# HighVoltageMeasurementModule_1000V_multi.net
KiCad netlist of a schematic drawn in EAGLE
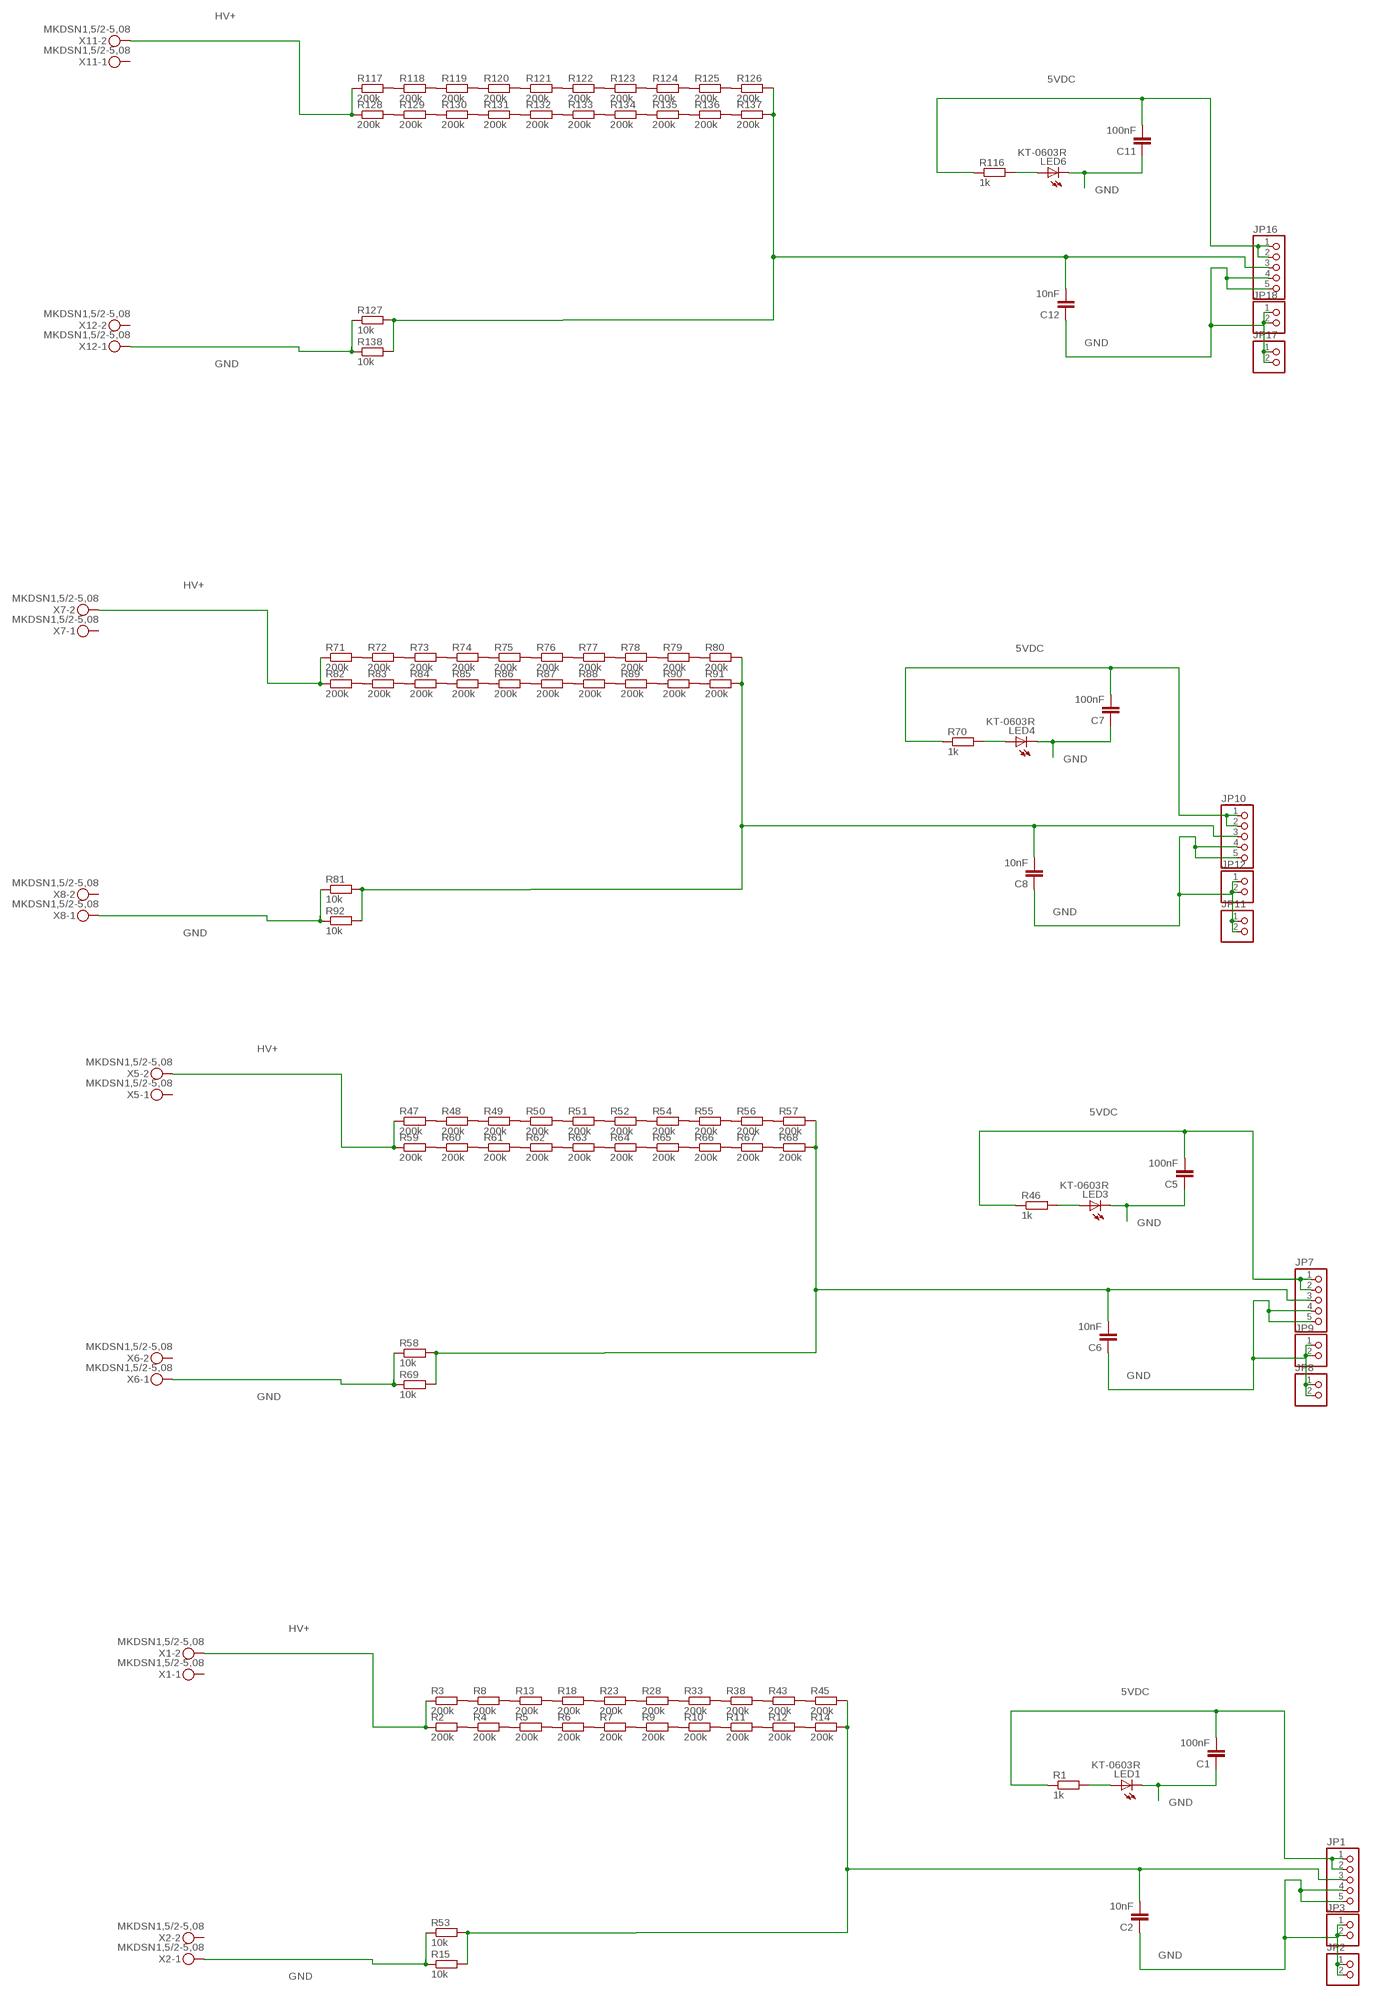
[diagram p0: schematic, sheet 1, part 1 of 3]
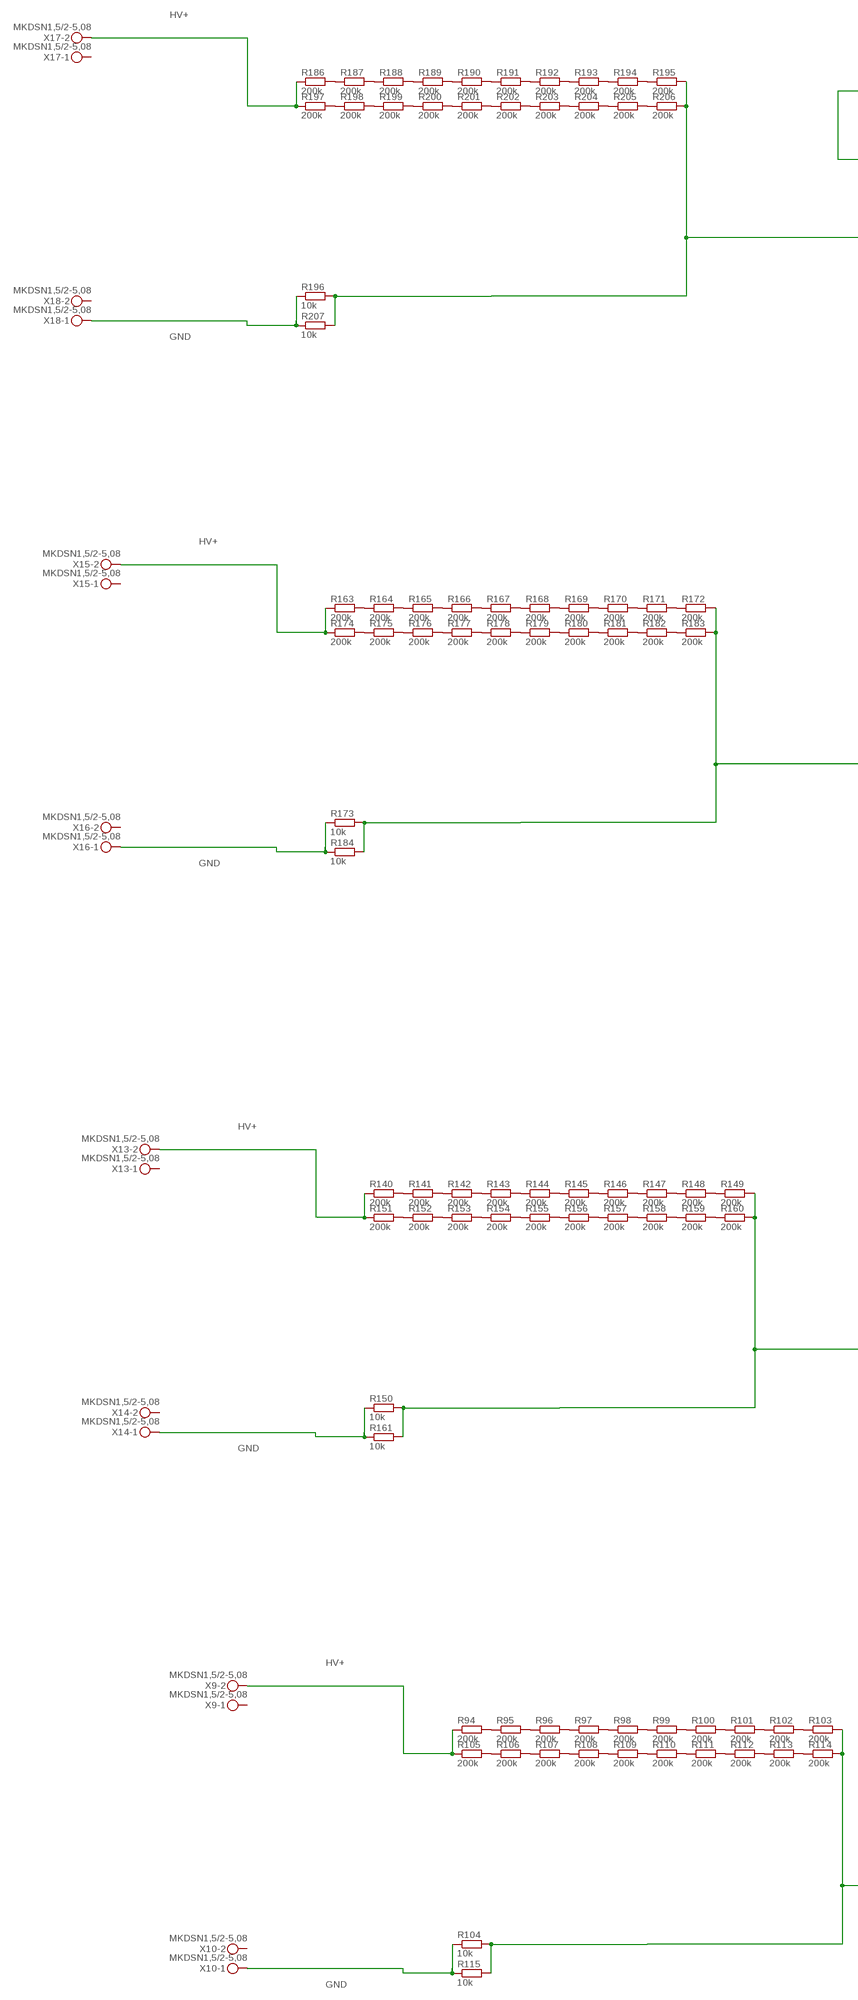
[diagram p1: schematic, sheet 1, part 2 of 3]
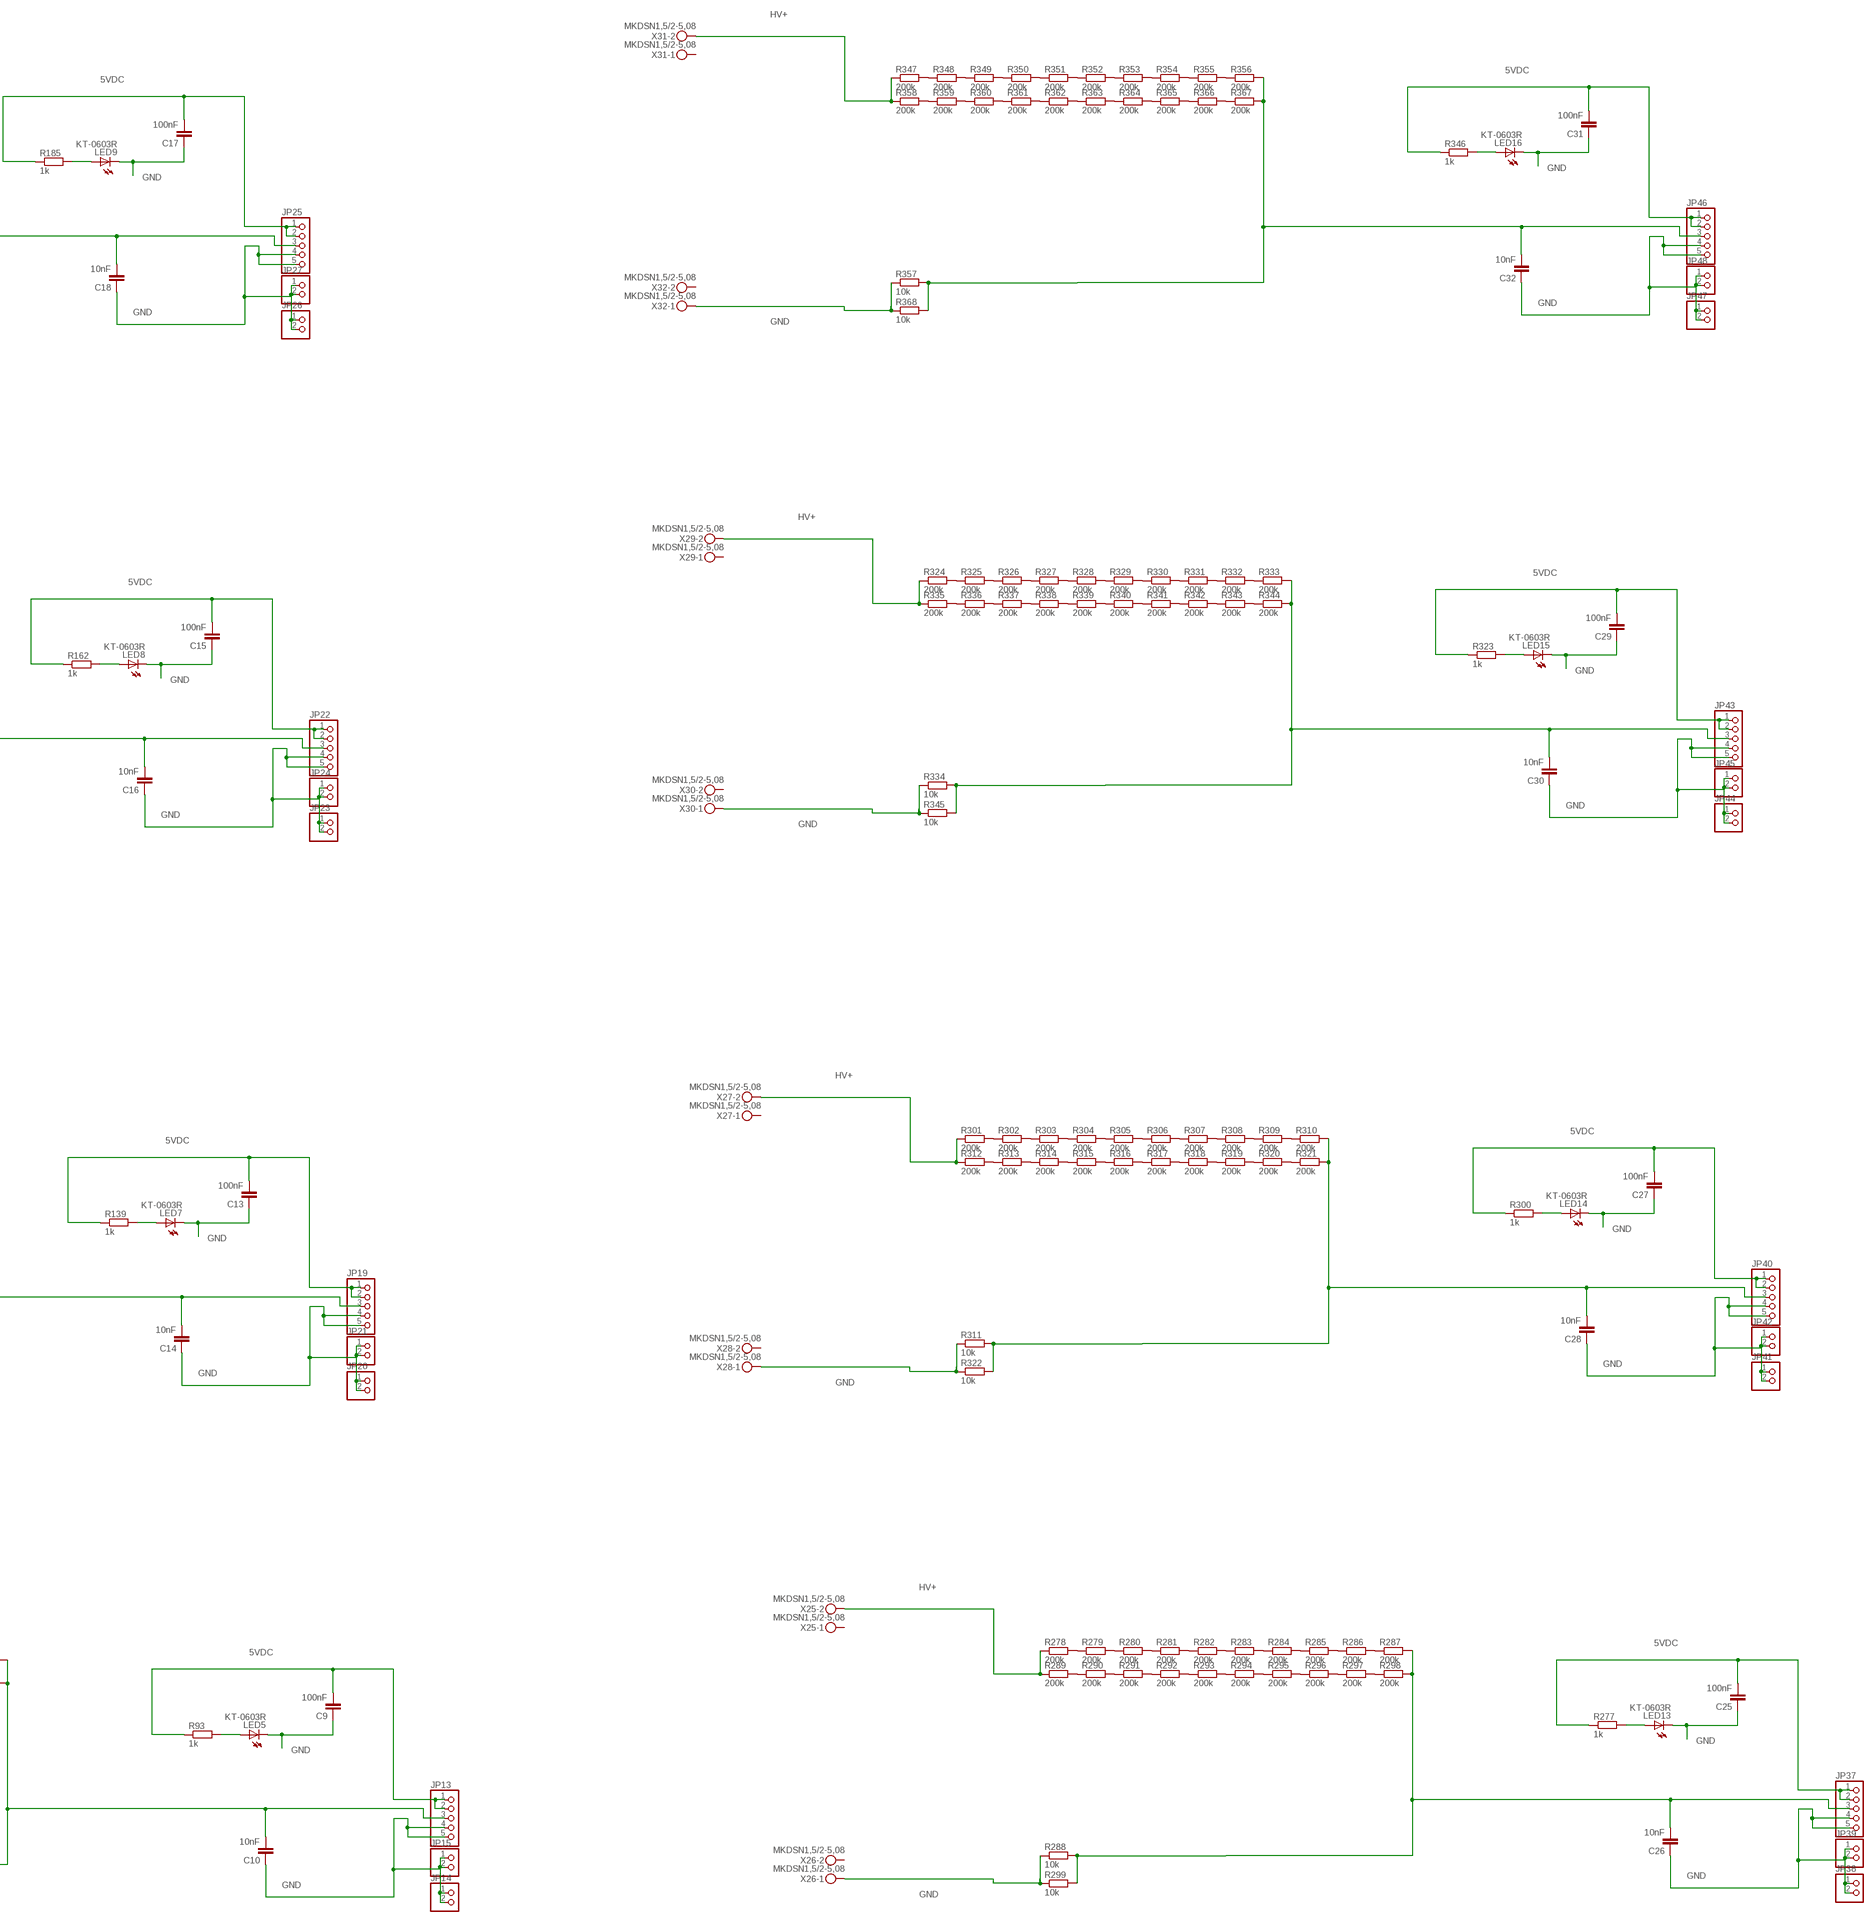
[diagram p2: schematic, sheet 1, part 3 of 3]

(export (version "E")
  (design (tool "Eeschema 10.0.6"))
  (components
    (comp (ref "C1")
      (value "100nF")
      (footprint "eagle-import:C0805")
      (libsource (lib "eagle-import") (part "C-EUC0805"))
    )
    (comp (ref "C2")
      (value "10nF")
      (footprint "eagle-import:C0805")
      (libsource (lib "eagle-import") (part "C-EUC0805"))
    )
    (comp (ref "C5")
      (value "100nF")
      (footprint "eagle-import:C0805")
      (libsource (lib "eagle-import") (part "C-EUC0805"))
    )
    (comp (ref "C6")
      (value "10nF")
      (footprint "eagle-import:C0805")
      (libsource (lib "eagle-import") (part "C-EUC0805"))
    )
    (comp (ref "C7")
      (value "100nF")
      (footprint "eagle-import:C0805")
      (libsource (lib "eagle-import") (part "C-EUC0805"))
    )
    (comp (ref "C8")
      (value "10nF")
      (footprint "eagle-import:C0805")
      (libsource (lib "eagle-import") (part "C-EUC0805"))
    )
    (comp (ref "C9")
      (value "100nF")
      (footprint "eagle-import:C0805")
      (libsource (lib "eagle-import") (part "C-EUC0805"))
    )
    (comp (ref "C10")
      (value "10nF")
      (footprint "eagle-import:C0805")
      (libsource (lib "eagle-import") (part "C-EUC0805"))
    )
    (comp (ref "C11")
      (value "100nF")
      (footprint "eagle-import:C0805")
      (libsource (lib "eagle-import") (part "C-EUC0805"))
    )
    (comp (ref "C12")
      (value "10nF")
      (footprint "eagle-import:C0805")
      (libsource (lib "eagle-import") (part "C-EUC0805"))
    )
    (comp (ref "C13")
      (value "100nF")
      (footprint "eagle-import:C0805")
      (libsource (lib "eagle-import") (part "C-EUC0805"))
    )
    (comp (ref "C14")
      (value "10nF")
      (footprint "eagle-import:C0805")
      (libsource (lib "eagle-import") (part "C-EUC0805"))
    )
    (comp (ref "C15")
      (value "100nF")
      (footprint "eagle-import:C0805")
      (libsource (lib "eagle-import") (part "C-EUC0805"))
    )
    (comp (ref "C16")
      (value "10nF")
      (footprint "eagle-import:C0805")
      (libsource (lib "eagle-import") (part "C-EUC0805"))
    )
    (comp (ref "C17")
      (value "100nF")
      (footprint "eagle-import:C0805")
      (libsource (lib "eagle-import") (part "C-EUC0805"))
    )
    (comp (ref "C18")
      (value "10nF")
      (footprint "eagle-import:C0805")
      (libsource (lib "eagle-import") (part "C-EUC0805"))
    )
    (comp (ref "C25")
      (value "100nF")
      (footprint "eagle-import:C0805")
      (libsource (lib "eagle-import") (part "C-EUC0805"))
    )
    (comp (ref "C26")
      (value "10nF")
      (footprint "eagle-import:C0805")
      (libsource (lib "eagle-import") (part "C-EUC0805"))
    )
    (comp (ref "C27")
      (value "100nF")
      (footprint "eagle-import:C0805")
      (libsource (lib "eagle-import") (part "C-EUC0805"))
    )
    (comp (ref "C28")
      (value "10nF")
      (footprint "eagle-import:C0805")
      (libsource (lib "eagle-import") (part "C-EUC0805"))
    )
    (comp (ref "C29")
      (value "100nF")
      (footprint "eagle-import:C0805")
      (libsource (lib "eagle-import") (part "C-EUC0805"))
    )
    (comp (ref "C30")
      (value "10nF")
      (footprint "eagle-import:C0805")
      (libsource (lib "eagle-import") (part "C-EUC0805"))
    )
    (comp (ref "C31")
      (value "100nF")
      (footprint "eagle-import:C0805")
      (libsource (lib "eagle-import") (part "C-EUC0805"))
    )
    (comp (ref "C32")
      (value "10nF")
      (footprint "eagle-import:C0805")
      (libsource (lib "eagle-import") (part "C-EUC0805"))
    )
    (comp (ref "JP1")
      (value "PINHD-1X5")
      (footprint "eagle-import:1X05")
      (libsource (lib "eagle-import") (part "PINHD-1X5"))
    )
    (comp (ref "JP2")
      (value "PINHD-1X2")
      (footprint "eagle-import:1X02")
      (libsource (lib "eagle-import") (part "PINHD-1X2"))
    )
    (comp (ref "JP3")
      (value "PINHD-1X2")
      (footprint "eagle-import:1X02")
      (libsource (lib "eagle-import") (part "PINHD-1X2"))
    )
    (comp (ref "JP7")
      (value "PINHD-1X5")
      (footprint "eagle-import:1X05")
      (libsource (lib "eagle-import") (part "PINHD-1X5"))
    )
    (comp (ref "JP8")
      (value "PINHD-1X2")
      (footprint "eagle-import:1X02")
      (libsource (lib "eagle-import") (part "PINHD-1X2"))
    )
    (comp (ref "JP9")
      (value "PINHD-1X2")
      (footprint "eagle-import:1X02")
      (libsource (lib "eagle-import") (part "PINHD-1X2"))
    )
    (comp (ref "JP10")
      (value "PINHD-1X5")
      (footprint "eagle-import:1X05")
      (libsource (lib "eagle-import") (part "PINHD-1X5"))
    )
    (comp (ref "JP11")
      (value "PINHD-1X2")
      (footprint "eagle-import:1X02")
      (libsource (lib "eagle-import") (part "PINHD-1X2"))
    )
    (comp (ref "JP12")
      (value "PINHD-1X2")
      (footprint "eagle-import:1X02")
      (libsource (lib "eagle-import") (part "PINHD-1X2"))
    )
    (comp (ref "JP13")
      (value "PINHD-1X5")
      (footprint "eagle-import:1X05")
      (libsource (lib "eagle-import") (part "PINHD-1X5"))
    )
    (comp (ref "JP14")
      (value "PINHD-1X2")
      (footprint "eagle-import:1X02")
      (libsource (lib "eagle-import") (part "PINHD-1X2"))
    )
    (comp (ref "JP15")
      (value "PINHD-1X2")
      (footprint "eagle-import:1X02")
      (libsource (lib "eagle-import") (part "PINHD-1X2"))
    )
    (comp (ref "JP16")
      (value "PINHD-1X5")
      (footprint "eagle-import:1X05")
      (libsource (lib "eagle-import") (part "PINHD-1X5"))
    )
    (comp (ref "JP17")
      (value "PINHD-1X2")
      (footprint "eagle-import:1X02")
      (libsource (lib "eagle-import") (part "PINHD-1X2"))
    )
    (comp (ref "JP18")
      (value "PINHD-1X2")
      (footprint "eagle-import:1X02")
      (libsource (lib "eagle-import") (part "PINHD-1X2"))
    )
    (comp (ref "JP19")
      (value "PINHD-1X5")
      (footprint "eagle-import:1X05")
      (libsource (lib "eagle-import") (part "PINHD-1X5"))
    )
    (comp (ref "JP20")
      (value "PINHD-1X2")
      (footprint "eagle-import:1X02")
      (libsource (lib "eagle-import") (part "PINHD-1X2"))
    )
    (comp (ref "JP21")
      (value "PINHD-1X2")
      (footprint "eagle-import:1X02")
      (libsource (lib "eagle-import") (part "PINHD-1X2"))
    )
    (comp (ref "JP22")
      (value "PINHD-1X5")
      (footprint "eagle-import:1X05")
      (libsource (lib "eagle-import") (part "PINHD-1X5"))
    )
    (comp (ref "JP23")
      (value "PINHD-1X2")
      (footprint "eagle-import:1X02")
      (libsource (lib "eagle-import") (part "PINHD-1X2"))
    )
    (comp (ref "JP24")
      (value "PINHD-1X2")
      (footprint "eagle-import:1X02")
      (libsource (lib "eagle-import") (part "PINHD-1X2"))
    )
    (comp (ref "JP25")
      (value "PINHD-1X5")
      (footprint "eagle-import:1X05")
      (libsource (lib "eagle-import") (part "PINHD-1X5"))
    )
    (comp (ref "JP26")
      (value "PINHD-1X2")
      (footprint "eagle-import:1X02")
      (libsource (lib "eagle-import") (part "PINHD-1X2"))
    )
    (comp (ref "JP27")
      (value "PINHD-1X2")
      (footprint "eagle-import:1X02")
      (libsource (lib "eagle-import") (part "PINHD-1X2"))
    )
    (comp (ref "JP37")
      (value "PINHD-1X5")
      (footprint "eagle-import:1X05")
      (libsource (lib "eagle-import") (part "PINHD-1X5"))
    )
    (comp (ref "JP38")
      (value "PINHD-1X2")
      (footprint "eagle-import:1X02")
      (libsource (lib "eagle-import") (part "PINHD-1X2"))
    )
    (comp (ref "JP39")
      (value "PINHD-1X2")
      (footprint "eagle-import:1X02")
      (libsource (lib "eagle-import") (part "PINHD-1X2"))
    )
    (comp (ref "JP40")
      (value "PINHD-1X5")
      (footprint "eagle-import:1X05")
      (libsource (lib "eagle-import") (part "PINHD-1X5"))
    )
    (comp (ref "JP41")
      (value "PINHD-1X2")
      (footprint "eagle-import:1X02")
      (libsource (lib "eagle-import") (part "PINHD-1X2"))
    )
    (comp (ref "JP42")
      (value "PINHD-1X2")
      (footprint "eagle-import:1X02")
      (libsource (lib "eagle-import") (part "PINHD-1X2"))
    )
    (comp (ref "JP43")
      (value "PINHD-1X5")
      (footprint "eagle-import:1X05")
      (libsource (lib "eagle-import") (part "PINHD-1X5"))
    )
    (comp (ref "JP44")
      (value "PINHD-1X2")
      (footprint "eagle-import:1X02")
      (libsource (lib "eagle-import") (part "PINHD-1X2"))
    )
    (comp (ref "JP45")
      (value "PINHD-1X2")
      (footprint "eagle-import:1X02")
      (libsource (lib "eagle-import") (part "PINHD-1X2"))
    )
    (comp (ref "JP46")
      (value "PINHD-1X5")
      (footprint "eagle-import:1X05")
      (libsource (lib "eagle-import") (part "PINHD-1X5"))
    )
    (comp (ref "JP47")
      (value "PINHD-1X2")
      (footprint "eagle-import:1X02")
      (libsource (lib "eagle-import") (part "PINHD-1X2"))
    )
    (comp (ref "JP48")
      (value "PINHD-1X2")
      (footprint "eagle-import:1X02")
      (libsource (lib "eagle-import") (part "PINHD-1X2"))
    )
    (comp (ref "LED1")
      (value "KT-0603R")
      (footprint "eagle-import:CHIPLED_0603")
      (libsource (lib "eagle-import") (part "LEDCHIPLED_0603"))
    )
    (comp (ref "LED3")
      (value "KT-0603R")
      (footprint "eagle-import:CHIPLED_0603")
      (libsource (lib "eagle-import") (part "LEDCHIPLED_0603"))
    )
    (comp (ref "LED4")
      (value "KT-0603R")
      (footprint "eagle-import:CHIPLED_0603")
      (libsource (lib "eagle-import") (part "LEDCHIPLED_0603"))
    )
    (comp (ref "LED5")
      (value "KT-0603R")
      (footprint "eagle-import:CHIPLED_0603")
      (libsource (lib "eagle-import") (part "LEDCHIPLED_0603"))
    )
    (comp (ref "LED6")
      (value "KT-0603R")
      (footprint "eagle-import:CHIPLED_0603")
      (libsource (lib "eagle-import") (part "LEDCHIPLED_0603"))
    )
    (comp (ref "LED7")
      (value "KT-0603R")
      (footprint "eagle-import:CHIPLED_0603")
      (libsource (lib "eagle-import") (part "LEDCHIPLED_0603"))
    )
    (comp (ref "LED8")
      (value "KT-0603R")
      (footprint "eagle-import:CHIPLED_0603")
      (libsource (lib "eagle-import") (part "LEDCHIPLED_0603"))
    )
    (comp (ref "LED9")
      (value "KT-0603R")
      (footprint "eagle-import:CHIPLED_0603")
      (libsource (lib "eagle-import") (part "LEDCHIPLED_0603"))
    )
    (comp (ref "LED13")
      (value "KT-0603R")
      (footprint "eagle-import:CHIPLED_0603")
      (libsource (lib "eagle-import") (part "LEDCHIPLED_0603"))
    )
    (comp (ref "LED14")
      (value "KT-0603R")
      (footprint "eagle-import:CHIPLED_0603")
      (libsource (lib "eagle-import") (part "LEDCHIPLED_0603"))
    )
    (comp (ref "LED15")
      (value "KT-0603R")
      (footprint "eagle-import:CHIPLED_0603")
      (libsource (lib "eagle-import") (part "LEDCHIPLED_0603"))
    )
    (comp (ref "LED16")
      (value "KT-0603R")
      (footprint "eagle-import:CHIPLED_0603")
      (libsource (lib "eagle-import") (part "LEDCHIPLED_0603"))
    )
    (comp (ref "R1")
      (value "1k")
      (footprint "eagle-import:R0805")
      (libsource (lib "eagle-import") (part "R-EU_R0805"))
    )
    (comp (ref "R2")
      (value "200k")
      (footprint "eagle-import:R0805")
      (libsource (lib "eagle-import") (part "R-EU_R0805"))
    )
    (comp (ref "R3")
      (value "200k")
      (footprint "eagle-import:R0805")
      (libsource (lib "eagle-import") (part "R-EU_R0805"))
    )
    (comp (ref "R4")
      (value "200k")
      (footprint "eagle-import:R0805")
      (libsource (lib "eagle-import") (part "R-EU_R0805"))
    )
    (comp (ref "R5")
      (value "200k")
      (footprint "eagle-import:R0805")
      (libsource (lib "eagle-import") (part "R-EU_R0805"))
    )
    (comp (ref "R6")
      (value "200k")
      (footprint "eagle-import:R0805")
      (libsource (lib "eagle-import") (part "R-EU_R0805"))
    )
    (comp (ref "R7")
      (value "200k")
      (footprint "eagle-import:R0805")
      (libsource (lib "eagle-import") (part "R-EU_R0805"))
    )
    (comp (ref "R8")
      (value "200k")
      (footprint "eagle-import:R0805")
      (libsource (lib "eagle-import") (part "R-EU_R0805"))
    )
    (comp (ref "R9")
      (value "200k")
      (footprint "eagle-import:R0805")
      (libsource (lib "eagle-import") (part "R-EU_R0805"))
    )
    (comp (ref "R10")
      (value "200k")
      (footprint "eagle-import:R0805")
      (libsource (lib "eagle-import") (part "R-EU_R0805"))
    )
    (comp (ref "R11")
      (value "200k")
      (footprint "eagle-import:R0805")
      (libsource (lib "eagle-import") (part "R-EU_R0805"))
    )
    (comp (ref "R12")
      (value "200k")
      (footprint "eagle-import:R0805")
      (libsource (lib "eagle-import") (part "R-EU_R0805"))
    )
    (comp (ref "R13")
      (value "200k")
      (footprint "eagle-import:R0805")
      (libsource (lib "eagle-import") (part "R-EU_R0805"))
    )
    (comp (ref "R14")
      (value "200k")
      (footprint "eagle-import:R0805")
      (libsource (lib "eagle-import") (part "R-EU_R0805"))
    )
    (comp (ref "R15")
      (value "10k")
      (footprint "eagle-import:R0805")
      (libsource (lib "eagle-import") (part "R-EU_R0805"))
    )
    (comp (ref "R18")
      (value "200k")
      (footprint "eagle-import:R0805")
      (libsource (lib "eagle-import") (part "R-EU_R0805"))
    )
    (comp (ref "R23")
      (value "200k")
      (footprint "eagle-import:R0805")
      (libsource (lib "eagle-import") (part "R-EU_R0805"))
    )
    (comp (ref "R28")
      (value "200k")
      (footprint "eagle-import:R0805")
      (libsource (lib "eagle-import") (part "R-EU_R0805"))
    )
    (comp (ref "R33")
      (value "200k")
      (footprint "eagle-import:R0805")
      (libsource (lib "eagle-import") (part "R-EU_R0805"))
    )
    (comp (ref "R38")
      (value "200k")
      (footprint "eagle-import:R0805")
      (libsource (lib "eagle-import") (part "R-EU_R0805"))
    )
    (comp (ref "R43")
      (value "200k")
      (footprint "eagle-import:R0805")
      (libsource (lib "eagle-import") (part "R-EU_R0805"))
    )
    (comp (ref "R45")
      (value "200k")
      (footprint "eagle-import:R0805")
      (libsource (lib "eagle-import") (part "R-EU_R0805"))
    )
    (comp (ref "R46")
      (value "1k")
      (footprint "eagle-import:R0805")
      (libsource (lib "eagle-import") (part "R-EU_R0805"))
    )
    (comp (ref "R47")
      (value "200k")
      (footprint "eagle-import:R0805")
      (libsource (lib "eagle-import") (part "R-EU_R0805"))
    )
    (comp (ref "R48")
      (value "200k")
      (footprint "eagle-import:R0805")
      (libsource (lib "eagle-import") (part "R-EU_R0805"))
    )
    (comp (ref "R49")
      (value "200k")
      (footprint "eagle-import:R0805")
      (libsource (lib "eagle-import") (part "R-EU_R0805"))
    )
    (comp (ref "R50")
      (value "200k")
      (footprint "eagle-import:R0805")
      (libsource (lib "eagle-import") (part "R-EU_R0805"))
    )
    (comp (ref "R51")
      (value "200k")
      (footprint "eagle-import:R0805")
      (libsource (lib "eagle-import") (part "R-EU_R0805"))
    )
    (comp (ref "R52")
      (value "200k")
      (footprint "eagle-import:R0805")
      (libsource (lib "eagle-import") (part "R-EU_R0805"))
    )
    (comp (ref "R53")
      (value "10k")
      (footprint "eagle-import:R0805")
      (libsource (lib "eagle-import") (part "R-EU_R0805"))
    )
    (comp (ref "R54")
      (value "200k")
      (footprint "eagle-import:R0805")
      (libsource (lib "eagle-import") (part "R-EU_R0805"))
    )
    (comp (ref "R55")
      (value "200k")
      (footprint "eagle-import:R0805")
      (libsource (lib "eagle-import") (part "R-EU_R0805"))
    )
    (comp (ref "R56")
      (value "200k")
      (footprint "eagle-import:R0805")
      (libsource (lib "eagle-import") (part "R-EU_R0805"))
    )
    (comp (ref "R57")
      (value "200k")
      (footprint "eagle-import:R0805")
      (libsource (lib "eagle-import") (part "R-EU_R0805"))
    )
    (comp (ref "R58")
      (value "10k")
      (footprint "eagle-import:R0805")
      (libsource (lib "eagle-import") (part "R-EU_R0805"))
    )
    (comp (ref "R59")
      (value "200k")
      (footprint "eagle-import:R0805")
      (libsource (lib "eagle-import") (part "R-EU_R0805"))
    )
    (comp (ref "R60")
      (value "200k")
      (footprint "eagle-import:R0805")
      (libsource (lib "eagle-import") (part "R-EU_R0805"))
    )
    (comp (ref "R61")
      (value "200k")
      (footprint "eagle-import:R0805")
      (libsource (lib "eagle-import") (part "R-EU_R0805"))
    )
    (comp (ref "R62")
      (value "200k")
      (footprint "eagle-import:R0805")
      (libsource (lib "eagle-import") (part "R-EU_R0805"))
    )
    (comp (ref "R63")
      (value "200k")
      (footprint "eagle-import:R0805")
      (libsource (lib "eagle-import") (part "R-EU_R0805"))
    )
    (comp (ref "R64")
      (value "200k")
      (footprint "eagle-import:R0805")
      (libsource (lib "eagle-import") (part "R-EU_R0805"))
    )
    (comp (ref "R65")
      (value "200k")
      (footprint "eagle-import:R0805")
      (libsource (lib "eagle-import") (part "R-EU_R0805"))
    )
    (comp (ref "R66")
      (value "200k")
      (footprint "eagle-import:R0805")
      (libsource (lib "eagle-import") (part "R-EU_R0805"))
    )
    (comp (ref "R67")
      (value "200k")
      (footprint "eagle-import:R0805")
      (libsource (lib "eagle-import") (part "R-EU_R0805"))
    )
    (comp (ref "R68")
      (value "200k")
      (footprint "eagle-import:R0805")
      (libsource (lib "eagle-import") (part "R-EU_R0805"))
    )
    (comp (ref "R69")
      (value "10k")
      (footprint "eagle-import:R0805")
      (libsource (lib "eagle-import") (part "R-EU_R0805"))
    )
    (comp (ref "R70")
      (value "1k")
      (footprint "eagle-import:R0805")
      (libsource (lib "eagle-import") (part "R-EU_R0805"))
    )
    (comp (ref "R71")
      (value "200k")
      (footprint "eagle-import:R0805")
      (libsource (lib "eagle-import") (part "R-EU_R0805"))
    )
    (comp (ref "R72")
      (value "200k")
      (footprint "eagle-import:R0805")
      (libsource (lib "eagle-import") (part "R-EU_R0805"))
    )
    (comp (ref "R73")
      (value "200k")
      (footprint "eagle-import:R0805")
      (libsource (lib "eagle-import") (part "R-EU_R0805"))
    )
    (comp (ref "R74")
      (value "200k")
      (footprint "eagle-import:R0805")
      (libsource (lib "eagle-import") (part "R-EU_R0805"))
    )
    (comp (ref "R75")
      (value "200k")
      (footprint "eagle-import:R0805")
      (libsource (lib "eagle-import") (part "R-EU_R0805"))
    )
    (comp (ref "R76")
      (value "200k")
      (footprint "eagle-import:R0805")
      (libsource (lib "eagle-import") (part "R-EU_R0805"))
    )
    (comp (ref "R77")
      (value "200k")
      (footprint "eagle-import:R0805")
      (libsource (lib "eagle-import") (part "R-EU_R0805"))
    )
    (comp (ref "R78")
      (value "200k")
      (footprint "eagle-import:R0805")
      (libsource (lib "eagle-import") (part "R-EU_R0805"))
    )
    (comp (ref "R79")
      (value "200k")
      (footprint "eagle-import:R0805")
      (libsource (lib "eagle-import") (part "R-EU_R0805"))
    )
    (comp (ref "R80")
      (value "200k")
      (footprint "eagle-import:R0805")
      (libsource (lib "eagle-import") (part "R-EU_R0805"))
    )
    (comp (ref "R81")
      (value "10k")
      (footprint "eagle-import:R0805")
      (libsource (lib "eagle-import") (part "R-EU_R0805"))
    )
    (comp (ref "R82")
      (value "200k")
      (footprint "eagle-import:R0805")
      (libsource (lib "eagle-import") (part "R-EU_R0805"))
    )
    (comp (ref "R83")
      (value "200k")
      (footprint "eagle-import:R0805")
      (libsource (lib "eagle-import") (part "R-EU_R0805"))
    )
    (comp (ref "R84")
      (value "200k")
      (footprint "eagle-import:R0805")
      (libsource (lib "eagle-import") (part "R-EU_R0805"))
    )
    (comp (ref "R85")
      (value "200k")
      (footprint "eagle-import:R0805")
      (libsource (lib "eagle-import") (part "R-EU_R0805"))
    )
    (comp (ref "R86")
      (value "200k")
      (footprint "eagle-import:R0805")
      (libsource (lib "eagle-import") (part "R-EU_R0805"))
    )
    (comp (ref "R87")
      (value "200k")
      (footprint "eagle-import:R0805")
      (libsource (lib "eagle-import") (part "R-EU_R0805"))
    )
    (comp (ref "R88")
      (value "200k")
      (footprint "eagle-import:R0805")
      (libsource (lib "eagle-import") (part "R-EU_R0805"))
    )
    (comp (ref "R89")
      (value "200k")
      (footprint "eagle-import:R0805")
      (libsource (lib "eagle-import") (part "R-EU_R0805"))
    )
    (comp (ref "R90")
      (value "200k")
      (footprint "eagle-import:R0805")
      (libsource (lib "eagle-import") (part "R-EU_R0805"))
    )
    (comp (ref "R91")
      (value "200k")
      (footprint "eagle-import:R0805")
      (libsource (lib "eagle-import") (part "R-EU_R0805"))
    )
    (comp (ref "R92")
      (value "10k")
      (footprint "eagle-import:R0805")
      (libsource (lib "eagle-import") (part "R-EU_R0805"))
    )
    (comp (ref "R93")
      (value "1k")
      (footprint "eagle-import:R0805")
      (libsource (lib "eagle-import") (part "R-EU_R0805"))
    )
    (comp (ref "R94")
      (value "200k")
      (footprint "eagle-import:R0805")
      (libsource (lib "eagle-import") (part "R-EU_R0805"))
    )
    (comp (ref "R95")
      (value "200k")
      (footprint "eagle-import:R0805")
      (libsource (lib "eagle-import") (part "R-EU_R0805"))
    )
    (comp (ref "R96")
      (value "200k")
      (footprint "eagle-import:R0805")
      (libsource (lib "eagle-import") (part "R-EU_R0805"))
    )
    (comp (ref "R97")
      (value "200k")
      (footprint "eagle-import:R0805")
      (libsource (lib "eagle-import") (part "R-EU_R0805"))
    )
    (comp (ref "R98")
      (value "200k")
      (footprint "eagle-import:R0805")
      (libsource (lib "eagle-import") (part "R-EU_R0805"))
    )
    (comp (ref "R99")
      (value "200k")
      (footprint "eagle-import:R0805")
      (libsource (lib "eagle-import") (part "R-EU_R0805"))
    )
    (comp (ref "R100")
      (value "200k")
      (footprint "eagle-import:R0805")
      (libsource (lib "eagle-import") (part "R-EU_R0805"))
    )
    (comp (ref "R101")
      (value "200k")
      (footprint "eagle-import:R0805")
      (libsource (lib "eagle-import") (part "R-EU_R0805"))
    )
    (comp (ref "R102")
      (value "200k")
      (footprint "eagle-import:R0805")
      (libsource (lib "eagle-import") (part "R-EU_R0805"))
    )
    (comp (ref "R103")
      (value "200k")
      (footprint "eagle-import:R0805")
      (libsource (lib "eagle-import") (part "R-EU_R0805"))
    )
    (comp (ref "R104")
      (value "10k")
      (footprint "eagle-import:R0805")
      (libsource (lib "eagle-import") (part "R-EU_R0805"))
    )
    (comp (ref "R105")
      (value "200k")
      (footprint "eagle-import:R0805")
      (libsource (lib "eagle-import") (part "R-EU_R0805"))
    )
    (comp (ref "R106")
      (value "200k")
      (footprint "eagle-import:R0805")
      (libsource (lib "eagle-import") (part "R-EU_R0805"))
    )
    (comp (ref "R107")
      (value "200k")
      (footprint "eagle-import:R0805")
      (libsource (lib "eagle-import") (part "R-EU_R0805"))
    )
    (comp (ref "R108")
      (value "200k")
      (footprint "eagle-import:R0805")
      (libsource (lib "eagle-import") (part "R-EU_R0805"))
    )
    (comp (ref "R109")
      (value "200k")
      (footprint "eagle-import:R0805")
      (libsource (lib "eagle-import") (part "R-EU_R0805"))
    )
    (comp (ref "R110")
      (value "200k")
      (footprint "eagle-import:R0805")
      (libsource (lib "eagle-import") (part "R-EU_R0805"))
    )
    (comp (ref "R111")
      (value "200k")
      (footprint "eagle-import:R0805")
      (libsource (lib "eagle-import") (part "R-EU_R0805"))
    )
    (comp (ref "R112")
      (value "200k")
      (footprint "eagle-import:R0805")
      (libsource (lib "eagle-import") (part "R-EU_R0805"))
    )
    (comp (ref "R113")
      (value "200k")
      (footprint "eagle-import:R0805")
      (libsource (lib "eagle-import") (part "R-EU_R0805"))
    )
    (comp (ref "R114")
      (value "200k")
      (footprint "eagle-import:R0805")
      (libsource (lib "eagle-import") (part "R-EU_R0805"))
    )
    (comp (ref "R115")
      (value "10k")
      (footprint "eagle-import:R0805")
      (libsource (lib "eagle-import") (part "R-EU_R0805"))
    )
    (comp (ref "R116")
      (value "1k")
      (footprint "eagle-import:R0805")
      (libsource (lib "eagle-import") (part "R-EU_R0805"))
    )
    (comp (ref "R117")
      (value "200k")
      (footprint "eagle-import:R0805")
      (libsource (lib "eagle-import") (part "R-EU_R0805"))
    )
    (comp (ref "R118")
      (value "200k")
      (footprint "eagle-import:R0805")
      (libsource (lib "eagle-import") (part "R-EU_R0805"))
    )
    (comp (ref "R119")
      (value "200k")
      (footprint "eagle-import:R0805")
      (libsource (lib "eagle-import") (part "R-EU_R0805"))
    )
    (comp (ref "R120")
      (value "200k")
      (footprint "eagle-import:R0805")
      (libsource (lib "eagle-import") (part "R-EU_R0805"))
    )
    (comp (ref "R121")
      (value "200k")
      (footprint "eagle-import:R0805")
      (libsource (lib "eagle-import") (part "R-EU_R0805"))
    )
    (comp (ref "R122")
      (value "200k")
      (footprint "eagle-import:R0805")
      (libsource (lib "eagle-import") (part "R-EU_R0805"))
    )
    (comp (ref "R123")
      (value "200k")
      (footprint "eagle-import:R0805")
      (libsource (lib "eagle-import") (part "R-EU_R0805"))
    )
    (comp (ref "R124")
      (value "200k")
      (footprint "eagle-import:R0805")
      (libsource (lib "eagle-import") (part "R-EU_R0805"))
    )
    (comp (ref "R125")
      (value "200k")
      (footprint "eagle-import:R0805")
      (libsource (lib "eagle-import") (part "R-EU_R0805"))
    )
    (comp (ref "R126")
      (value "200k")
      (footprint "eagle-import:R0805")
      (libsource (lib "eagle-import") (part "R-EU_R0805"))
    )
    (comp (ref "R127")
      (value "10k")
      (footprint "eagle-import:R0805")
      (libsource (lib "eagle-import") (part "R-EU_R0805"))
    )
    (comp (ref "R128")
      (value "200k")
      (footprint "eagle-import:R0805")
      (libsource (lib "eagle-import") (part "R-EU_R0805"))
    )
    (comp (ref "R129")
      (value "200k")
      (footprint "eagle-import:R0805")
      (libsource (lib "eagle-import") (part "R-EU_R0805"))
    )
    (comp (ref "R130")
      (value "200k")
      (footprint "eagle-import:R0805")
      (libsource (lib "eagle-import") (part "R-EU_R0805"))
    )
    (comp (ref "R131")
      (value "200k")
      (footprint "eagle-import:R0805")
      (libsource (lib "eagle-import") (part "R-EU_R0805"))
    )
    (comp (ref "R132")
      (value "200k")
      (footprint "eagle-import:R0805")
      (libsource (lib "eagle-import") (part "R-EU_R0805"))
    )
    (comp (ref "R133")
      (value "200k")
      (footprint "eagle-import:R0805")
      (libsource (lib "eagle-import") (part "R-EU_R0805"))
    )
    (comp (ref "R134")
      (value "200k")
      (footprint "eagle-import:R0805")
      (libsource (lib "eagle-import") (part "R-EU_R0805"))
    )
    (comp (ref "R135")
      (value "200k")
      (footprint "eagle-import:R0805")
      (libsource (lib "eagle-import") (part "R-EU_R0805"))
    )
    (comp (ref "R136")
      (value "200k")
      (footprint "eagle-import:R0805")
      (libsource (lib "eagle-import") (part "R-EU_R0805"))
    )
    (comp (ref "R137")
      (value "200k")
      (footprint "eagle-import:R0805")
      (libsource (lib "eagle-import") (part "R-EU_R0805"))
    )
    (comp (ref "R138")
      (value "10k")
      (footprint "eagle-import:R0805")
      (libsource (lib "eagle-import") (part "R-EU_R0805"))
    )
    (comp (ref "R139")
      (value "1k")
      (footprint "eagle-import:R0805")
      (libsource (lib "eagle-import") (part "R-EU_R0805"))
    )
    (comp (ref "R140")
      (value "200k")
      (footprint "eagle-import:R0805")
      (libsource (lib "eagle-import") (part "R-EU_R0805"))
    )
    (comp (ref "R141")
      (value "200k")
      (footprint "eagle-import:R0805")
      (libsource (lib "eagle-import") (part "R-EU_R0805"))
    )
    (comp (ref "R142")
      (value "200k")
      (footprint "eagle-import:R0805")
      (libsource (lib "eagle-import") (part "R-EU_R0805"))
    )
    (comp (ref "R143")
      (value "200k")
      (footprint "eagle-import:R0805")
      (libsource (lib "eagle-import") (part "R-EU_R0805"))
    )
    (comp (ref "R144")
      (value "200k")
      (footprint "eagle-import:R0805")
      (libsource (lib "eagle-import") (part "R-EU_R0805"))
    )
    (comp (ref "R145")
      (value "200k")
      (footprint "eagle-import:R0805")
      (libsource (lib "eagle-import") (part "R-EU_R0805"))
    )
    (comp (ref "R146")
      (value "200k")
      (footprint "eagle-import:R0805")
      (libsource (lib "eagle-import") (part "R-EU_R0805"))
    )
    (comp (ref "R147")
      (value "200k")
      (footprint "eagle-import:R0805")
      (libsource (lib "eagle-import") (part "R-EU_R0805"))
    )
    (comp (ref "R148")
      (value "200k")
      (footprint "eagle-import:R0805")
      (libsource (lib "eagle-import") (part "R-EU_R0805"))
    )
    (comp (ref "R149")
      (value "200k")
      (footprint "eagle-import:R0805")
      (libsource (lib "eagle-import") (part "R-EU_R0805"))
    )
    (comp (ref "R150")
      (value "10k")
      (footprint "eagle-import:R0805")
      (libsource (lib "eagle-import") (part "R-EU_R0805"))
    )
    (comp (ref "R151")
      (value "200k")
      (footprint "eagle-import:R0805")
      (libsource (lib "eagle-import") (part "R-EU_R0805"))
    )
    (comp (ref "R152")
      (value "200k")
      (footprint "eagle-import:R0805")
      (libsource (lib "eagle-import") (part "R-EU_R0805"))
    )
    (comp (ref "R153")
      (value "200k")
      (footprint "eagle-import:R0805")
      (libsource (lib "eagle-import") (part "R-EU_R0805"))
    )
    (comp (ref "R154")
      (value "200k")
      (footprint "eagle-import:R0805")
      (libsource (lib "eagle-import") (part "R-EU_R0805"))
    )
    (comp (ref "R155")
      (value "200k")
      (footprint "eagle-import:R0805")
      (libsource (lib "eagle-import") (part "R-EU_R0805"))
    )
    (comp (ref "R156")
      (value "200k")
      (footprint "eagle-import:R0805")
      (libsource (lib "eagle-import") (part "R-EU_R0805"))
    )
    (comp (ref "R157")
      (value "200k")
      (footprint "eagle-import:R0805")
      (libsource (lib "eagle-import") (part "R-EU_R0805"))
    )
    (comp (ref "R158")
      (value "200k")
      (footprint "eagle-import:R0805")
      (libsource (lib "eagle-import") (part "R-EU_R0805"))
    )
    (comp (ref "R159")
      (value "200k")
      (footprint "eagle-import:R0805")
      (libsource (lib "eagle-import") (part "R-EU_R0805"))
    )
    (comp (ref "R160")
      (value "200k")
      (footprint "eagle-import:R0805")
      (libsource (lib "eagle-import") (part "R-EU_R0805"))
    )
    (comp (ref "R161")
      (value "10k")
      (footprint "eagle-import:R0805")
      (libsource (lib "eagle-import") (part "R-EU_R0805"))
    )
    (comp (ref "R162")
      (value "1k")
      (footprint "eagle-import:R0805")
      (libsource (lib "eagle-import") (part "R-EU_R0805"))
    )
    (comp (ref "R163")
      (value "200k")
      (footprint "eagle-import:R0805")
      (libsource (lib "eagle-import") (part "R-EU_R0805"))
    )
    (comp (ref "R164")
      (value "200k")
      (footprint "eagle-import:R0805")
      (libsource (lib "eagle-import") (part "R-EU_R0805"))
    )
    (comp (ref "R165")
      (value "200k")
      (footprint "eagle-import:R0805")
      (libsource (lib "eagle-import") (part "R-EU_R0805"))
    )
    (comp (ref "R166")
      (value "200k")
      (footprint "eagle-import:R0805")
      (libsource (lib "eagle-import") (part "R-EU_R0805"))
    )
    (comp (ref "R167")
      (value "200k")
      (footprint "eagle-import:R0805")
      (libsource (lib "eagle-import") (part "R-EU_R0805"))
    )
    (comp (ref "R168")
      (value "200k")
      (footprint "eagle-import:R0805")
      (libsource (lib "eagle-import") (part "R-EU_R0805"))
    )
    (comp (ref "R169")
      (value "200k")
      (footprint "eagle-import:R0805")
      (libsource (lib "eagle-import") (part "R-EU_R0805"))
    )
    (comp (ref "R170")
      (value "200k")
      (footprint "eagle-import:R0805")
      (libsource (lib "eagle-import") (part "R-EU_R0805"))
    )
    (comp (ref "R171")
      (value "200k")
      (footprint "eagle-import:R0805")
      (libsource (lib "eagle-import") (part "R-EU_R0805"))
    )
    (comp (ref "R172")
      (value "200k")
      (footprint "eagle-import:R0805")
      (libsource (lib "eagle-import") (part "R-EU_R0805"))
    )
    (comp (ref "R173")
      (value "10k")
      (footprint "eagle-import:R0805")
      (libsource (lib "eagle-import") (part "R-EU_R0805"))
    )
    (comp (ref "R174")
      (value "200k")
      (footprint "eagle-import:R0805")
      (libsource (lib "eagle-import") (part "R-EU_R0805"))
    )
    (comp (ref "R175")
      (value "200k")
      (footprint "eagle-import:R0805")
      (libsource (lib "eagle-import") (part "R-EU_R0805"))
    )
    (comp (ref "R176")
      (value "200k")
      (footprint "eagle-import:R0805")
      (libsource (lib "eagle-import") (part "R-EU_R0805"))
    )
    (comp (ref "R177")
      (value "200k")
      (footprint "eagle-import:R0805")
      (libsource (lib "eagle-import") (part "R-EU_R0805"))
    )
    (comp (ref "R178")
      (value "200k")
      (footprint "eagle-import:R0805")
      (libsource (lib "eagle-import") (part "R-EU_R0805"))
    )
    (comp (ref "R179")
      (value "200k")
      (footprint "eagle-import:R0805")
      (libsource (lib "eagle-import") (part "R-EU_R0805"))
    )
    (comp (ref "R180")
      (value "200k")
      (footprint "eagle-import:R0805")
      (libsource (lib "eagle-import") (part "R-EU_R0805"))
    )
    (comp (ref "R181")
      (value "200k")
      (footprint "eagle-import:R0805")
      (libsource (lib "eagle-import") (part "R-EU_R0805"))
    )
    (comp (ref "R182")
      (value "200k")
      (footprint "eagle-import:R0805")
      (libsource (lib "eagle-import") (part "R-EU_R0805"))
    )
    (comp (ref "R183")
      (value "200k")
      (footprint "eagle-import:R0805")
      (libsource (lib "eagle-import") (part "R-EU_R0805"))
    )
    (comp (ref "R184")
      (value "10k")
      (footprint "eagle-import:R0805")
      (libsource (lib "eagle-import") (part "R-EU_R0805"))
    )
    (comp (ref "R185")
      (value "1k")
      (footprint "eagle-import:R0805")
      (libsource (lib "eagle-import") (part "R-EU_R0805"))
    )
    (comp (ref "R186")
      (value "200k")
      (footprint "eagle-import:R0805")
      (libsource (lib "eagle-import") (part "R-EU_R0805"))
    )
    (comp (ref "R187")
      (value "200k")
      (footprint "eagle-import:R0805")
      (libsource (lib "eagle-import") (part "R-EU_R0805"))
    )
    (comp (ref "R188")
      (value "200k")
      (footprint "eagle-import:R0805")
      (libsource (lib "eagle-import") (part "R-EU_R0805"))
    )
    (comp (ref "R189")
      (value "200k")
      (footprint "eagle-import:R0805")
      (libsource (lib "eagle-import") (part "R-EU_R0805"))
    )
    (comp (ref "R190")
      (value "200k")
      (footprint "eagle-import:R0805")
      (libsource (lib "eagle-import") (part "R-EU_R0805"))
    )
    (comp (ref "R191")
      (value "200k")
      (footprint "eagle-import:R0805")
      (libsource (lib "eagle-import") (part "R-EU_R0805"))
    )
    (comp (ref "R192")
      (value "200k")
      (footprint "eagle-import:R0805")
      (libsource (lib "eagle-import") (part "R-EU_R0805"))
    )
    (comp (ref "R193")
      (value "200k")
      (footprint "eagle-import:R0805")
      (libsource (lib "eagle-import") (part "R-EU_R0805"))
    )
    (comp (ref "R194")
      (value "200k")
      (footprint "eagle-import:R0805")
      (libsource (lib "eagle-import") (part "R-EU_R0805"))
    )
    (comp (ref "R195")
      (value "200k")
      (footprint "eagle-import:R0805")
      (libsource (lib "eagle-import") (part "R-EU_R0805"))
    )
    (comp (ref "R196")
      (value "10k")
      (footprint "eagle-import:R0805")
      (libsource (lib "eagle-import") (part "R-EU_R0805"))
    )
    (comp (ref "R197")
      (value "200k")
      (footprint "eagle-import:R0805")
      (libsource (lib "eagle-import") (part "R-EU_R0805"))
    )
    (comp (ref "R198")
      (value "200k")
      (footprint "eagle-import:R0805")
      (libsource (lib "eagle-import") (part "R-EU_R0805"))
    )
    (comp (ref "R199")
      (value "200k")
      (footprint "eagle-import:R0805")
      (libsource (lib "eagle-import") (part "R-EU_R0805"))
    )
    (comp (ref "R200")
      (value "200k")
      (footprint "eagle-import:R0805")
      (libsource (lib "eagle-import") (part "R-EU_R0805"))
    )
    (comp (ref "R201")
      (value "200k")
      (footprint "eagle-import:R0805")
      (libsource (lib "eagle-import") (part "R-EU_R0805"))
    )
    (comp (ref "R202")
      (value "200k")
      (footprint "eagle-import:R0805")
      (libsource (lib "eagle-import") (part "R-EU_R0805"))
    )
    (comp (ref "R203")
      (value "200k")
      (footprint "eagle-import:R0805")
      (libsource (lib "eagle-import") (part "R-EU_R0805"))
    )
    (comp (ref "R204")
      (value "200k")
      (footprint "eagle-import:R0805")
      (libsource (lib "eagle-import") (part "R-EU_R0805"))
    )
    (comp (ref "R205")
      (value "200k")
      (footprint "eagle-import:R0805")
      (libsource (lib "eagle-import") (part "R-EU_R0805"))
    )
    (comp (ref "R206")
      (value "200k")
      (footprint "eagle-import:R0805")
      (libsource (lib "eagle-import") (part "R-EU_R0805"))
    )
    (comp (ref "R207")
      (value "10k")
      (footprint "eagle-import:R0805")
      (libsource (lib "eagle-import") (part "R-EU_R0805"))
    )
    (comp (ref "R277")
      (value "1k")
      (footprint "eagle-import:R0805")
      (libsource (lib "eagle-import") (part "R-EU_R0805"))
    )
    (comp (ref "R278")
      (value "200k")
      (footprint "eagle-import:R0805")
      (libsource (lib "eagle-import") (part "R-EU_R0805"))
    )
    (comp (ref "R279")
      (value "200k")
      (footprint "eagle-import:R0805")
      (libsource (lib "eagle-import") (part "R-EU_R0805"))
    )
    (comp (ref "R280")
      (value "200k")
      (footprint "eagle-import:R0805")
      (libsource (lib "eagle-import") (part "R-EU_R0805"))
    )
    (comp (ref "R281")
      (value "200k")
      (footprint "eagle-import:R0805")
      (libsource (lib "eagle-import") (part "R-EU_R0805"))
    )
    (comp (ref "R282")
      (value "200k")
      (footprint "eagle-import:R0805")
      (libsource (lib "eagle-import") (part "R-EU_R0805"))
    )
    (comp (ref "R283")
      (value "200k")
      (footprint "eagle-import:R0805")
      (libsource (lib "eagle-import") (part "R-EU_R0805"))
    )
    (comp (ref "R284")
      (value "200k")
      (footprint "eagle-import:R0805")
      (libsource (lib "eagle-import") (part "R-EU_R0805"))
    )
    (comp (ref "R285")
      (value "200k")
      (footprint "eagle-import:R0805")
      (libsource (lib "eagle-import") (part "R-EU_R0805"))
    )
    (comp (ref "R286")
      (value "200k")
      (footprint "eagle-import:R0805")
      (libsource (lib "eagle-import") (part "R-EU_R0805"))
    )
    (comp (ref "R287")
      (value "200k")
      (footprint "eagle-import:R0805")
      (libsource (lib "eagle-import") (part "R-EU_R0805"))
    )
    (comp (ref "R288")
      (value "10k")
      (footprint "eagle-import:R0805")
      (libsource (lib "eagle-import") (part "R-EU_R0805"))
    )
    (comp (ref "R289")
      (value "200k")
      (footprint "eagle-import:R0805")
      (libsource (lib "eagle-import") (part "R-EU_R0805"))
    )
    (comp (ref "R290")
      (value "200k")
      (footprint "eagle-import:R0805")
      (libsource (lib "eagle-import") (part "R-EU_R0805"))
    )
    (comp (ref "R291")
      (value "200k")
      (footprint "eagle-import:R0805")
      (libsource (lib "eagle-import") (part "R-EU_R0805"))
    )
    (comp (ref "R292")
      (value "200k")
      (footprint "eagle-import:R0805")
      (libsource (lib "eagle-import") (part "R-EU_R0805"))
    )
    (comp (ref "R293")
      (value "200k")
      (footprint "eagle-import:R0805")
      (libsource (lib "eagle-import") (part "R-EU_R0805"))
    )
    (comp (ref "R294")
      (value "200k")
      (footprint "eagle-import:R0805")
      (libsource (lib "eagle-import") (part "R-EU_R0805"))
    )
    (comp (ref "R295")
      (value "200k")
      (footprint "eagle-import:R0805")
      (libsource (lib "eagle-import") (part "R-EU_R0805"))
    )
    (comp (ref "R296")
      (value "200k")
      (footprint "eagle-import:R0805")
      (libsource (lib "eagle-import") (part "R-EU_R0805"))
    )
    (comp (ref "R297")
      (value "200k")
      (footprint "eagle-import:R0805")
      (libsource (lib "eagle-import") (part "R-EU_R0805"))
    )
    (comp (ref "R298")
      (value "200k")
      (footprint "eagle-import:R0805")
      (libsource (lib "eagle-import") (part "R-EU_R0805"))
    )
    (comp (ref "R299")
      (value "10k")
      (footprint "eagle-import:R0805")
      (libsource (lib "eagle-import") (part "R-EU_R0805"))
    )
    (comp (ref "R300")
      (value "1k")
      (footprint "eagle-import:R0805")
      (libsource (lib "eagle-import") (part "R-EU_R0805"))
    )
    (comp (ref "R301")
      (value "200k")
      (footprint "eagle-import:R0805")
      (libsource (lib "eagle-import") (part "R-EU_R0805"))
    )
    (comp (ref "R302")
      (value "200k")
      (footprint "eagle-import:R0805")
      (libsource (lib "eagle-import") (part "R-EU_R0805"))
    )
    (comp (ref "R303")
      (value "200k")
      (footprint "eagle-import:R0805")
      (libsource (lib "eagle-import") (part "R-EU_R0805"))
    )
    (comp (ref "R304")
      (value "200k")
      (footprint "eagle-import:R0805")
      (libsource (lib "eagle-import") (part "R-EU_R0805"))
    )
    (comp (ref "R305")
      (value "200k")
      (footprint "eagle-import:R0805")
      (libsource (lib "eagle-import") (part "R-EU_R0805"))
    )
    (comp (ref "R306")
      (value "200k")
      (footprint "eagle-import:R0805")
      (libsource (lib "eagle-import") (part "R-EU_R0805"))
    )
    (comp (ref "R307")
      (value "200k")
      (footprint "eagle-import:R0805")
      (libsource (lib "eagle-import") (part "R-EU_R0805"))
    )
    (comp (ref "R308")
      (value "200k")
      (footprint "eagle-import:R0805")
      (libsource (lib "eagle-import") (part "R-EU_R0805"))
    )
    (comp (ref "R309")
      (value "200k")
      (footprint "eagle-import:R0805")
      (libsource (lib "eagle-import") (part "R-EU_R0805"))
    )
    (comp (ref "R310")
      (value "200k")
      (footprint "eagle-import:R0805")
      (libsource (lib "eagle-import") (part "R-EU_R0805"))
    )
    (comp (ref "R311")
      (value "10k")
      (footprint "eagle-import:R0805")
      (libsource (lib "eagle-import") (part "R-EU_R0805"))
    )
    (comp (ref "R312")
      (value "200k")
      (footprint "eagle-import:R0805")
      (libsource (lib "eagle-import") (part "R-EU_R0805"))
    )
    (comp (ref "R313")
      (value "200k")
      (footprint "eagle-import:R0805")
      (libsource (lib "eagle-import") (part "R-EU_R0805"))
    )
    (comp (ref "R314")
      (value "200k")
      (footprint "eagle-import:R0805")
      (libsource (lib "eagle-import") (part "R-EU_R0805"))
    )
    (comp (ref "R315")
      (value "200k")
      (footprint "eagle-import:R0805")
      (libsource (lib "eagle-import") (part "R-EU_R0805"))
    )
    (comp (ref "R316")
      (value "200k")
      (footprint "eagle-import:R0805")
      (libsource (lib "eagle-import") (part "R-EU_R0805"))
    )
    (comp (ref "R317")
      (value "200k")
      (footprint "eagle-import:R0805")
      (libsource (lib "eagle-import") (part "R-EU_R0805"))
    )
    (comp (ref "R318")
      (value "200k")
      (footprint "eagle-import:R0805")
      (libsource (lib "eagle-import") (part "R-EU_R0805"))
    )
    (comp (ref "R319")
      (value "200k")
      (footprint "eagle-import:R0805")
      (libsource (lib "eagle-import") (part "R-EU_R0805"))
    )
    (comp (ref "R320")
      (value "200k")
      (footprint "eagle-import:R0805")
      (libsource (lib "eagle-import") (part "R-EU_R0805"))
    )
    (comp (ref "R321")
      (value "200k")
      (footprint "eagle-import:R0805")
      (libsource (lib "eagle-import") (part "R-EU_R0805"))
    )
    (comp (ref "R322")
      (value "10k")
      (footprint "eagle-import:R0805")
      (libsource (lib "eagle-import") (part "R-EU_R0805"))
    )
    (comp (ref "R323")
      (value "1k")
      (footprint "eagle-import:R0805")
      (libsource (lib "eagle-import") (part "R-EU_R0805"))
    )
    (comp (ref "R324")
      (value "200k")
      (footprint "eagle-import:R0805")
      (libsource (lib "eagle-import") (part "R-EU_R0805"))
    )
    (comp (ref "R325")
      (value "200k")
      (footprint "eagle-import:R0805")
      (libsource (lib "eagle-import") (part "R-EU_R0805"))
    )
    (comp (ref "R326")
      (value "200k")
      (footprint "eagle-import:R0805")
      (libsource (lib "eagle-import") (part "R-EU_R0805"))
    )
    (comp (ref "R327")
      (value "200k")
      (footprint "eagle-import:R0805")
      (libsource (lib "eagle-import") (part "R-EU_R0805"))
    )
    (comp (ref "R328")
      (value "200k")
      (footprint "eagle-import:R0805")
      (libsource (lib "eagle-import") (part "R-EU_R0805"))
    )
    (comp (ref "R329")
      (value "200k")
      (footprint "eagle-import:R0805")
      (libsource (lib "eagle-import") (part "R-EU_R0805"))
    )
    (comp (ref "R330")
      (value "200k")
      (footprint "eagle-import:R0805")
      (libsource (lib "eagle-import") (part "R-EU_R0805"))
    )
    (comp (ref "R331")
      (value "200k")
      (footprint "eagle-import:R0805")
      (libsource (lib "eagle-import") (part "R-EU_R0805"))
    )
    (comp (ref "R332")
      (value "200k")
      (footprint "eagle-import:R0805")
      (libsource (lib "eagle-import") (part "R-EU_R0805"))
    )
    (comp (ref "R333")
      (value "200k")
      (footprint "eagle-import:R0805")
      (libsource (lib "eagle-import") (part "R-EU_R0805"))
    )
    (comp (ref "R334")
      (value "10k")
      (footprint "eagle-import:R0805")
      (libsource (lib "eagle-import") (part "R-EU_R0805"))
    )
    (comp (ref "R335")
      (value "200k")
      (footprint "eagle-import:R0805")
      (libsource (lib "eagle-import") (part "R-EU_R0805"))
    )
    (comp (ref "R336")
      (value "200k")
      (footprint "eagle-import:R0805")
      (libsource (lib "eagle-import") (part "R-EU_R0805"))
    )
    (comp (ref "R337")
      (value "200k")
      (footprint "eagle-import:R0805")
      (libsource (lib "eagle-import") (part "R-EU_R0805"))
    )
    (comp (ref "R338")
      (value "200k")
      (footprint "eagle-import:R0805")
      (libsource (lib "eagle-import") (part "R-EU_R0805"))
    )
    (comp (ref "R339")
      (value "200k")
      (footprint "eagle-import:R0805")
      (libsource (lib "eagle-import") (part "R-EU_R0805"))
    )
    (comp (ref "R340")
      (value "200k")
      (footprint "eagle-import:R0805")
      (libsource (lib "eagle-import") (part "R-EU_R0805"))
    )
    (comp (ref "R341")
      (value "200k")
      (footprint "eagle-import:R0805")
      (libsource (lib "eagle-import") (part "R-EU_R0805"))
    )
    (comp (ref "R342")
      (value "200k")
      (footprint "eagle-import:R0805")
      (libsource (lib "eagle-import") (part "R-EU_R0805"))
    )
    (comp (ref "R343")
      (value "200k")
      (footprint "eagle-import:R0805")
      (libsource (lib "eagle-import") (part "R-EU_R0805"))
    )
    (comp (ref "R344")
      (value "200k")
      (footprint "eagle-import:R0805")
      (libsource (lib "eagle-import") (part "R-EU_R0805"))
    )
    (comp (ref "R345")
      (value "10k")
      (footprint "eagle-import:R0805")
      (libsource (lib "eagle-import") (part "R-EU_R0805"))
    )
    (comp (ref "R346")
      (value "1k")
      (footprint "eagle-import:R0805")
      (libsource (lib "eagle-import") (part "R-EU_R0805"))
    )
    (comp (ref "R347")
      (value "200k")
      (footprint "eagle-import:R0805")
      (libsource (lib "eagle-import") (part "R-EU_R0805"))
    )
    (comp (ref "R348")
      (value "200k")
      (footprint "eagle-import:R0805")
      (libsource (lib "eagle-import") (part "R-EU_R0805"))
    )
    (comp (ref "R349")
      (value "200k")
      (footprint "eagle-import:R0805")
      (libsource (lib "eagle-import") (part "R-EU_R0805"))
    )
    (comp (ref "R350")
      (value "200k")
      (footprint "eagle-import:R0805")
      (libsource (lib "eagle-import") (part "R-EU_R0805"))
    )
    (comp (ref "R351")
      (value "200k")
      (footprint "eagle-import:R0805")
      (libsource (lib "eagle-import") (part "R-EU_R0805"))
    )
    (comp (ref "R352")
      (value "200k")
      (footprint "eagle-import:R0805")
      (libsource (lib "eagle-import") (part "R-EU_R0805"))
    )
    (comp (ref "R353")
      (value "200k")
      (footprint "eagle-import:R0805")
      (libsource (lib "eagle-import") (part "R-EU_R0805"))
    )
    (comp (ref "R354")
      (value "200k")
      (footprint "eagle-import:R0805")
      (libsource (lib "eagle-import") (part "R-EU_R0805"))
    )
    (comp (ref "R355")
      (value "200k")
      (footprint "eagle-import:R0805")
      (libsource (lib "eagle-import") (part "R-EU_R0805"))
    )
    (comp (ref "R356")
      (value "200k")
      (footprint "eagle-import:R0805")
      (libsource (lib "eagle-import") (part "R-EU_R0805"))
    )
    (comp (ref "R357")
      (value "10k")
      (footprint "eagle-import:R0805")
      (libsource (lib "eagle-import") (part "R-EU_R0805"))
    )
    (comp (ref "R358")
      (value "200k")
      (footprint "eagle-import:R0805")
      (libsource (lib "eagle-import") (part "R-EU_R0805"))
    )
    (comp (ref "R359")
      (value "200k")
      (footprint "eagle-import:R0805")
      (libsource (lib "eagle-import") (part "R-EU_R0805"))
    )
    (comp (ref "R360")
      (value "200k")
      (footprint "eagle-import:R0805")
      (libsource (lib "eagle-import") (part "R-EU_R0805"))
    )
    (comp (ref "R361")
      (value "200k")
      (footprint "eagle-import:R0805")
      (libsource (lib "eagle-import") (part "R-EU_R0805"))
    )
    (comp (ref "R362")
      (value "200k")
      (footprint "eagle-import:R0805")
      (libsource (lib "eagle-import") (part "R-EU_R0805"))
    )
    (comp (ref "R363")
      (value "200k")
      (footprint "eagle-import:R0805")
      (libsource (lib "eagle-import") (part "R-EU_R0805"))
    )
    (comp (ref "R364")
      (value "200k")
      (footprint "eagle-import:R0805")
      (libsource (lib "eagle-import") (part "R-EU_R0805"))
    )
    (comp (ref "R365")
      (value "200k")
      (footprint "eagle-import:R0805")
      (libsource (lib "eagle-import") (part "R-EU_R0805"))
    )
    (comp (ref "R366")
      (value "200k")
      (footprint "eagle-import:R0805")
      (libsource (lib "eagle-import") (part "R-EU_R0805"))
    )
    (comp (ref "R367")
      (value "200k")
      (footprint "eagle-import:R0805")
      (libsource (lib "eagle-import") (part "R-EU_R0805"))
    )
    (comp (ref "R368")
      (value "10k")
      (footprint "eagle-import:R0805")
      (libsource (lib "eagle-import") (part "R-EU_R0805"))
    )
    (comp (ref "X1")
      (value "MKDSN1,5/2-5,08")
      (footprint "eagle-import:MKDSN1,5_2-5,08")
      (libsource (lib "eagle-import") (part "MKDSN1,5/2-5,08"))
    )
    (comp (ref "X2")
      (value "MKDSN1,5/2-5,08")
      (footprint "eagle-import:MKDSN1,5_2-5,08")
      (libsource (lib "eagle-import") (part "MKDSN1,5/2-5,08"))
    )
    (comp (ref "X5")
      (value "MKDSN1,5/2-5,08")
      (footprint "eagle-import:MKDSN1,5_2-5,08")
      (libsource (lib "eagle-import") (part "MKDSN1,5/2-5,08"))
    )
    (comp (ref "X6")
      (value "MKDSN1,5/2-5,08")
      (footprint "eagle-import:MKDSN1,5_2-5,08")
      (libsource (lib "eagle-import") (part "MKDSN1,5/2-5,08"))
    )
    (comp (ref "X7")
      (value "MKDSN1,5/2-5,08")
      (footprint "eagle-import:MKDSN1,5_2-5,08")
      (libsource (lib "eagle-import") (part "MKDSN1,5/2-5,08"))
    )
    (comp (ref "X8")
      (value "MKDSN1,5/2-5,08")
      (footprint "eagle-import:MKDSN1,5_2-5,08")
      (libsource (lib "eagle-import") (part "MKDSN1,5/2-5,08"))
    )
    (comp (ref "X9")
      (value "MKDSN1,5/2-5,08")
      (footprint "eagle-import:MKDSN1,5_2-5,08")
      (libsource (lib "eagle-import") (part "MKDSN1,5/2-5,08"))
    )
    (comp (ref "X10")
      (value "MKDSN1,5/2-5,08")
      (footprint "eagle-import:MKDSN1,5_2-5,08")
      (libsource (lib "eagle-import") (part "MKDSN1,5/2-5,08"))
    )
    (comp (ref "X11")
      (value "MKDSN1,5/2-5,08")
      (footprint "eagle-import:MKDSN1,5_2-5,08")
      (libsource (lib "eagle-import") (part "MKDSN1,5/2-5,08"))
    )
    (comp (ref "X12")
      (value "MKDSN1,5/2-5,08")
      (footprint "eagle-import:MKDSN1,5_2-5,08")
      (libsource (lib "eagle-import") (part "MKDSN1,5/2-5,08"))
    )
    (comp (ref "X13")
      (value "MKDSN1,5/2-5,08")
      (footprint "eagle-import:MKDSN1,5_2-5,08")
      (libsource (lib "eagle-import") (part "MKDSN1,5/2-5,08"))
    )
    (comp (ref "X14")
      (value "MKDSN1,5/2-5,08")
      (footprint "eagle-import:MKDSN1,5_2-5,08")
      (libsource (lib "eagle-import") (part "MKDSN1,5/2-5,08"))
    )
    (comp (ref "X15")
      (value "MKDSN1,5/2-5,08")
      (footprint "eagle-import:MKDSN1,5_2-5,08")
      (libsource (lib "eagle-import") (part "MKDSN1,5/2-5,08"))
    )
    (comp (ref "X16")
      (value "MKDSN1,5/2-5,08")
      (footprint "eagle-import:MKDSN1,5_2-5,08")
      (libsource (lib "eagle-import") (part "MKDSN1,5/2-5,08"))
    )
    (comp (ref "X17")
      (value "MKDSN1,5/2-5,08")
      (footprint "eagle-import:MKDSN1,5_2-5,08")
      (libsource (lib "eagle-import") (part "MKDSN1,5/2-5,08"))
    )
    (comp (ref "X18")
      (value "MKDSN1,5/2-5,08")
      (footprint "eagle-import:MKDSN1,5_2-5,08")
      (libsource (lib "eagle-import") (part "MKDSN1,5/2-5,08"))
    )
    (comp (ref "X25")
      (value "MKDSN1,5/2-5,08")
      (footprint "eagle-import:MKDSN1,5_2-5,08")
      (libsource (lib "eagle-import") (part "MKDSN1,5/2-5,08"))
    )
    (comp (ref "X26")
      (value "MKDSN1,5/2-5,08")
      (footprint "eagle-import:MKDSN1,5_2-5,08")
      (libsource (lib "eagle-import") (part "MKDSN1,5/2-5,08"))
    )
    (comp (ref "X27")
      (value "MKDSN1,5/2-5,08")
      (footprint "eagle-import:MKDSN1,5_2-5,08")
      (libsource (lib "eagle-import") (part "MKDSN1,5/2-5,08"))
    )
    (comp (ref "X28")
      (value "MKDSN1,5/2-5,08")
      (footprint "eagle-import:MKDSN1,5_2-5,08")
      (libsource (lib "eagle-import") (part "MKDSN1,5/2-5,08"))
    )
    (comp (ref "X29")
      (value "MKDSN1,5/2-5,08")
      (footprint "eagle-import:MKDSN1,5_2-5,08")
      (libsource (lib "eagle-import") (part "MKDSN1,5/2-5,08"))
    )
    (comp (ref "X30")
      (value "MKDSN1,5/2-5,08")
      (footprint "eagle-import:MKDSN1,5_2-5,08")
      (libsource (lib "eagle-import") (part "MKDSN1,5/2-5,08"))
    )
    (comp (ref "X31")
      (value "MKDSN1,5/2-5,08")
      (footprint "eagle-import:MKDSN1,5_2-5,08")
      (libsource (lib "eagle-import") (part "MKDSN1,5/2-5,08"))
    )
    (comp (ref "X32")
      (value "MKDSN1,5/2-5,08")
      (footprint "eagle-import:MKDSN1,5_2-5,08")
      (libsource (lib "eagle-import") (part "MKDSN1,5/2-5,08"))
    )
  )
  (nets
    (net (code "1") (name "5VDC") (class "Default")
      (node (ref "C1") (pin "2") (pinfunction "2_2") (pintype "passive"))
      (node (ref "C11") (pin "2") (pinfunction "2_2") (pintype "passive"))
      (node (ref "C13") (pin "2") (pinfunction "2_2") (pintype "passive"))
      (node (ref "C15") (pin "2") (pinfunction "2_2") (pintype "passive"))
      (node (ref "C17") (pin "2") (pinfunction "2_2") (pintype "passive"))
      (node (ref "C25") (pin "2") (pinfunction "2_2") (pintype "passive"))
      (node (ref "C27") (pin "2") (pinfunction "2_2") (pintype "passive"))
      (node (ref "C29") (pin "2") (pinfunction "2_2") (pintype "passive"))
      (node (ref "C31") (pin "2") (pinfunction "2_2") (pintype "passive"))
      (node (ref "C5") (pin "2") (pinfunction "2_2") (pintype "passive"))
      (node (ref "C7") (pin "2") (pinfunction "2_2") (pintype "passive"))
      (node (ref "C9") (pin "2") (pinfunction "2_2") (pintype "passive"))
      (node (ref "JP1") (pin "1") (pinfunction "1_1") (pintype "passive"))
      (node (ref "JP1") (pin "2") (pinfunction "2_2") (pintype "passive"))
      (node (ref "JP10") (pin "1") (pinfunction "1_1") (pintype "passive"))
      (node (ref "JP10") (pin "2") (pinfunction "2_2") (pintype "passive"))
      (node (ref "JP13") (pin "1") (pinfunction "1_1") (pintype "passive"))
      (node (ref "JP13") (pin "2") (pinfunction "2_2") (pintype "passive"))
      (node (ref "JP16") (pin "1") (pinfunction "1_1") (pintype "passive"))
      (node (ref "JP16") (pin "2") (pinfunction "2_2") (pintype "passive"))
      (node (ref "JP19") (pin "1") (pinfunction "1_1") (pintype "passive"))
      (node (ref "JP19") (pin "2") (pinfunction "2_2") (pintype "passive"))
      (node (ref "JP22") (pin "1") (pinfunction "1_1") (pintype "passive"))
      (node (ref "JP22") (pin "2") (pinfunction "2_2") (pintype "passive"))
      (node (ref "JP25") (pin "1") (pinfunction "1_1") (pintype "passive"))
      (node (ref "JP25") (pin "2") (pinfunction "2_2") (pintype "passive"))
      (node (ref "JP37") (pin "1") (pinfunction "1_1") (pintype "passive"))
      (node (ref "JP37") (pin "2") (pinfunction "2_2") (pintype "passive"))
      (node (ref "JP40") (pin "1") (pinfunction "1_1") (pintype "passive"))
      (node (ref "JP40") (pin "2") (pinfunction "2_2") (pintype "passive"))
      (node (ref "JP43") (pin "1") (pinfunction "1_1") (pintype "passive"))
      (node (ref "JP43") (pin "2") (pinfunction "2_2") (pintype "passive"))
      (node (ref "JP46") (pin "1") (pinfunction "1_1") (pintype "passive"))
      (node (ref "JP46") (pin "2") (pinfunction "2_2") (pintype "passive"))
      (node (ref "JP7") (pin "1") (pinfunction "1_1") (pintype "passive"))
      (node (ref "JP7") (pin "2") (pinfunction "2_2") (pintype "passive"))
      (node (ref "R1") (pin "1") (pinfunction "1_1") (pintype "passive"))
      (node (ref "R116") (pin "1") (pinfunction "1_1") (pintype "passive"))
      (node (ref "R139") (pin "1") (pinfunction "1_1") (pintype "passive"))
      (node (ref "R162") (pin "1") (pinfunction "1_1") (pintype "passive"))
      (node (ref "R185") (pin "1") (pinfunction "1_1") (pintype "passive"))
      (node (ref "R277") (pin "1") (pinfunction "1_1") (pintype "passive"))
      (node (ref "R300") (pin "1") (pinfunction "1_1") (pintype "passive"))
      (node (ref "R323") (pin "1") (pinfunction "1_1") (pintype "passive"))
      (node (ref "R346") (pin "1") (pinfunction "1_1") (pintype "passive"))
      (node (ref "R46") (pin "1") (pinfunction "1_1") (pintype "passive"))
      (node (ref "R70") (pin "1") (pinfunction "1_1") (pintype "passive"))
      (node (ref "R93") (pin "1") (pinfunction "1_1") (pintype "passive"))
    )
    (net (code "2") (name "GND") (class "Default")
      (node (ref "C1") (pin "1") (pinfunction "1_1") (pintype "passive"))
      (node (ref "C10") (pin "1") (pinfunction "1_1") (pintype "passive"))
      (node (ref "C11") (pin "1") (pinfunction "1_1") (pintype "passive"))
      (node (ref "C12") (pin "1") (pinfunction "1_1") (pintype "passive"))
      (node (ref "C13") (pin "1") (pinfunction "1_1") (pintype "passive"))
      (node (ref "C14") (pin "1") (pinfunction "1_1") (pintype "passive"))
      (node (ref "C15") (pin "1") (pinfunction "1_1") (pintype "passive"))
      (node (ref "C16") (pin "1") (pinfunction "1_1") (pintype "passive"))
      (node (ref "C17") (pin "1") (pinfunction "1_1") (pintype "passive"))
      (node (ref "C18") (pin "1") (pinfunction "1_1") (pintype "passive"))
      (node (ref "C2") (pin "1") (pinfunction "1_1") (pintype "passive"))
      (node (ref "C25") (pin "1") (pinfunction "1_1") (pintype "passive"))
      (node (ref "C26") (pin "1") (pinfunction "1_1") (pintype "passive"))
      (node (ref "C27") (pin "1") (pinfunction "1_1") (pintype "passive"))
      (node (ref "C28") (pin "1") (pinfunction "1_1") (pintype "passive"))
      (node (ref "C29") (pin "1") (pinfunction "1_1") (pintype "passive"))
      (node (ref "C30") (pin "1") (pinfunction "1_1") (pintype "passive"))
      (node (ref "C31") (pin "1") (pinfunction "1_1") (pintype "passive"))
      (node (ref "C32") (pin "1") (pinfunction "1_1") (pintype "passive"))
      (node (ref "C5") (pin "1") (pinfunction "1_1") (pintype "passive"))
      (node (ref "C6") (pin "1") (pinfunction "1_1") (pintype "passive"))
      (node (ref "C7") (pin "1") (pinfunction "1_1") (pintype "passive"))
      (node (ref "C8") (pin "1") (pinfunction "1_1") (pintype "passive"))
      (node (ref "C9") (pin "1") (pinfunction "1_1") (pintype "passive"))
      (node (ref "JP1") (pin "4") (pinfunction "4_4") (pintype "passive"))
      (node (ref "JP1") (pin "5") (pinfunction "5_5") (pintype "passive"))
      (node (ref "JP10") (pin "4") (pinfunction "4_4") (pintype "passive"))
      (node (ref "JP10") (pin "5") (pinfunction "5_5") (pintype "passive"))
      (node (ref "JP11") (pin "1") (pinfunction "1_1") (pintype "passive"))
      (node (ref "JP11") (pin "2") (pinfunction "2_2") (pintype "passive"))
      (node (ref "JP12") (pin "1") (pinfunction "1_1") (pintype "passive"))
      (node (ref "JP12") (pin "2") (pinfunction "2_2") (pintype "passive"))
      (node (ref "JP13") (pin "4") (pinfunction "4_4") (pintype "passive"))
      (node (ref "JP13") (pin "5") (pinfunction "5_5") (pintype "passive"))
      (node (ref "JP14") (pin "1") (pinfunction "1_1") (pintype "passive"))
      (node (ref "JP14") (pin "2") (pinfunction "2_2") (pintype "passive"))
      (node (ref "JP15") (pin "1") (pinfunction "1_1") (pintype "passive"))
      (node (ref "JP15") (pin "2") (pinfunction "2_2") (pintype "passive"))
      (node (ref "JP16") (pin "4") (pinfunction "4_4") (pintype "passive"))
      (node (ref "JP16") (pin "5") (pinfunction "5_5") (pintype "passive"))
      (node (ref "JP17") (pin "1") (pinfunction "1_1") (pintype "passive"))
      (node (ref "JP17") (pin "2") (pinfunction "2_2") (pintype "passive"))
      (node (ref "JP18") (pin "1") (pinfunction "1_1") (pintype "passive"))
      (node (ref "JP18") (pin "2") (pinfunction "2_2") (pintype "passive"))
      (node (ref "JP19") (pin "4") (pinfunction "4_4") (pintype "passive"))
      (node (ref "JP19") (pin "5") (pinfunction "5_5") (pintype "passive"))
      (node (ref "JP2") (pin "1") (pinfunction "1_1") (pintype "passive"))
      (node (ref "JP2") (pin "2") (pinfunction "2_2") (pintype "passive"))
      (node (ref "JP20") (pin "1") (pinfunction "1_1") (pintype "passive"))
      (node (ref "JP20") (pin "2") (pinfunction "2_2") (pintype "passive"))
      (node (ref "JP21") (pin "1") (pinfunction "1_1") (pintype "passive"))
      (node (ref "JP21") (pin "2") (pinfunction "2_2") (pintype "passive"))
      (node (ref "JP22") (pin "4") (pinfunction "4_4") (pintype "passive"))
      (node (ref "JP22") (pin "5") (pinfunction "5_5") (pintype "passive"))
      (node (ref "JP23") (pin "1") (pinfunction "1_1") (pintype "passive"))
      (node (ref "JP23") (pin "2") (pinfunction "2_2") (pintype "passive"))
      (node (ref "JP24") (pin "1") (pinfunction "1_1") (pintype "passive"))
      (node (ref "JP24") (pin "2") (pinfunction "2_2") (pintype "passive"))
      (node (ref "JP25") (pin "4") (pinfunction "4_4") (pintype "passive"))
      (node (ref "JP25") (pin "5") (pinfunction "5_5") (pintype "passive"))
      (node (ref "JP26") (pin "1") (pinfunction "1_1") (pintype "passive"))
      (node (ref "JP26") (pin "2") (pinfunction "2_2") (pintype "passive"))
      (node (ref "JP27") (pin "1") (pinfunction "1_1") (pintype "passive"))
      (node (ref "JP27") (pin "2") (pinfunction "2_2") (pintype "passive"))
      (node (ref "JP3") (pin "1") (pinfunction "1_1") (pintype "passive"))
      (node (ref "JP3") (pin "2") (pinfunction "2_2") (pintype "passive"))
      (node (ref "JP37") (pin "4") (pinfunction "4_4") (pintype "passive"))
      (node (ref "JP37") (pin "5") (pinfunction "5_5") (pintype "passive"))
      (node (ref "JP38") (pin "1") (pinfunction "1_1") (pintype "passive"))
      (node (ref "JP38") (pin "2") (pinfunction "2_2") (pintype "passive"))
      (node (ref "JP39") (pin "1") (pinfunction "1_1") (pintype "passive"))
      (node (ref "JP39") (pin "2") (pinfunction "2_2") (pintype "passive"))
      (node (ref "JP40") (pin "4") (pinfunction "4_4") (pintype "passive"))
      (node (ref "JP40") (pin "5") (pinfunction "5_5") (pintype "passive"))
      (node (ref "JP41") (pin "1") (pinfunction "1_1") (pintype "passive"))
      (node (ref "JP41") (pin "2") (pinfunction "2_2") (pintype "passive"))
      (node (ref "JP42") (pin "1") (pinfunction "1_1") (pintype "passive"))
      (node (ref "JP42") (pin "2") (pinfunction "2_2") (pintype "passive"))
      (node (ref "JP43") (pin "4") (pinfunction "4_4") (pintype "passive"))
      (node (ref "JP43") (pin "5") (pinfunction "5_5") (pintype "passive"))
      (node (ref "JP44") (pin "1") (pinfunction "1_1") (pintype "passive"))
      (node (ref "JP44") (pin "2") (pinfunction "2_2") (pintype "passive"))
      (node (ref "JP45") (pin "1") (pinfunction "1_1") (pintype "passive"))
      (node (ref "JP45") (pin "2") (pinfunction "2_2") (pintype "passive"))
      (node (ref "JP46") (pin "4") (pinfunction "4_4") (pintype "passive"))
      (node (ref "JP46") (pin "5") (pinfunction "5_5") (pintype "passive"))
      (node (ref "JP47") (pin "1") (pinfunction "1_1") (pintype "passive"))
      (node (ref "JP47") (pin "2") (pinfunction "2_2") (pintype "passive"))
      (node (ref "JP48") (pin "1") (pinfunction "1_1") (pintype "passive"))
      (node (ref "JP48") (pin "2") (pinfunction "2_2") (pintype "passive"))
      (node (ref "JP7") (pin "4") (pinfunction "4_4") (pintype "passive"))
      (node (ref "JP7") (pin "5") (pinfunction "5_5") (pintype "passive"))
      (node (ref "JP8") (pin "1") (pinfunction "1_1") (pintype "passive"))
      (node (ref "JP8") (pin "2") (pinfunction "2_2") (pintype "passive"))
      (node (ref "JP9") (pin "1") (pinfunction "1_1") (pintype "passive"))
      (node (ref "JP9") (pin "2") (pinfunction "2_2") (pintype "passive"))
      (node (ref "LED1") (pin "C") (pinfunction "C_C") (pintype "passive"))
      (node (ref "LED13") (pin "C") (pinfunction "C_C") (pintype "passive"))
      (node (ref "LED14") (pin "C") (pinfunction "C_C") (pintype "passive"))
      (node (ref "LED15") (pin "C") (pinfunction "C_C") (pintype "passive"))
      (node (ref "LED16") (pin "C") (pinfunction "C_C") (pintype "passive"))
      (node (ref "LED3") (pin "C") (pinfunction "C_C") (pintype "passive"))
      (node (ref "LED4") (pin "C") (pinfunction "C_C") (pintype "passive"))
      (node (ref "LED5") (pin "C") (pinfunction "C_C") (pintype "passive"))
      (node (ref "LED6") (pin "C") (pinfunction "C_C") (pintype "passive"))
      (node (ref "LED7") (pin "C") (pinfunction "C_C") (pintype "passive"))
      (node (ref "LED8") (pin "C") (pinfunction "C_C") (pintype "passive"))
      (node (ref "LED9") (pin "C") (pinfunction "C_C") (pintype "passive"))
      (node (ref "R104") (pin "1") (pinfunction "1_1") (pintype "passive"))
      (node (ref "R115") (pin "1") (pinfunction "1_1") (pintype "passive"))
      (node (ref "R127") (pin "1") (pinfunction "1_1") (pintype "passive"))
      (node (ref "R138") (pin "1") (pinfunction "1_1") (pintype "passive"))
      (node (ref "R15") (pin "1") (pinfunction "1_1") (pintype "passive"))
      (node (ref "R150") (pin "1") (pinfunction "1_1") (pintype "passive"))
      (node (ref "R161") (pin "1") (pinfunction "1_1") (pintype "passive"))
      (node (ref "R173") (pin "1") (pinfunction "1_1") (pintype "passive"))
      (node (ref "R184") (pin "1") (pinfunction "1_1") (pintype "passive"))
      (node (ref "R196") (pin "1") (pinfunction "1_1") (pintype "passive"))
      (node (ref "R207") (pin "1") (pinfunction "1_1") (pintype "passive"))
      (node (ref "R288") (pin "1") (pinfunction "1_1") (pintype "passive"))
      (node (ref "R299") (pin "1") (pinfunction "1_1") (pintype "passive"))
      (node (ref "R311") (pin "1") (pinfunction "1_1") (pintype "passive"))
      (node (ref "R322") (pin "1") (pinfunction "1_1") (pintype "passive"))
      (node (ref "R334") (pin "1") (pinfunction "1_1") (pintype "passive"))
      (node (ref "R345") (pin "1") (pinfunction "1_1") (pintype "passive"))
      (node (ref "R357") (pin "1") (pinfunction "1_1") (pintype "passive"))
      (node (ref "R368") (pin "1") (pinfunction "1_1") (pintype "passive"))
      (node (ref "R53") (pin "1") (pinfunction "1_1") (pintype "passive"))
      (node (ref "R58") (pin "1") (pinfunction "1_1") (pintype "passive"))
      (node (ref "R69") (pin "1") (pinfunction "1_1") (pintype "passive"))
      (node (ref "R81") (pin "1") (pinfunction "1_1") (pintype "passive"))
      (node (ref "R92") (pin "1") (pinfunction "1_1") (pintype "passive"))
      (node (ref "X10") (pin "1") (pinfunction "KL_1") (pintype "passive"))
      (node (ref "X12") (pin "1") (pinfunction "KL_1") (pintype "passive"))
      (node (ref "X14") (pin "1") (pinfunction "KL_1") (pintype "passive"))
      (node (ref "X16") (pin "1") (pinfunction "KL_1") (pintype "passive"))
      (node (ref "X18") (pin "1") (pinfunction "KL_1") (pintype "passive"))
      (node (ref "X2") (pin "1") (pinfunction "KL_1") (pintype "passive"))
      (node (ref "X26") (pin "1") (pinfunction "KL_1") (pintype "passive"))
      (node (ref "X28") (pin "1") (pinfunction "KL_1") (pintype "passive"))
      (node (ref "X30") (pin "1") (pinfunction "KL_1") (pintype "passive"))
      (node (ref "X32") (pin "1") (pinfunction "KL_1") (pintype "passive"))
      (node (ref "X6") (pin "1") (pinfunction "KL_1") (pintype "passive"))
      (node (ref "X8") (pin "1") (pinfunction "KL_1") (pintype "passive"))
    )
    (net (code "3") (name "HV+") (class "Default")
      (node (ref "R105") (pin "1") (pinfunction "1_1") (pintype "passive"))
      (node (ref "R117") (pin "1") (pinfunction "1_1") (pintype "passive"))
      (node (ref "R128") (pin "1") (pinfunction "1_1") (pintype "passive"))
      (node (ref "R140") (pin "1") (pinfunction "1_1") (pintype "passive"))
      (node (ref "R151") (pin "1") (pinfunction "1_1") (pintype "passive"))
      (node (ref "R163") (pin "1") (pinfunction "1_1") (pintype "passive"))
      (node (ref "R174") (pin "1") (pinfunction "1_1") (pintype "passive"))
      (node (ref "R186") (pin "1") (pinfunction "1_1") (pintype "passive"))
      (node (ref "R197") (pin "1") (pinfunction "1_1") (pintype "passive"))
      (node (ref "R2") (pin "1") (pinfunction "1_1") (pintype "passive"))
      (node (ref "R278") (pin "1") (pinfunction "1_1") (pintype "passive"))
      (node (ref "R289") (pin "1") (pinfunction "1_1") (pintype "passive"))
      (node (ref "R3") (pin "1") (pinfunction "1_1") (pintype "passive"))
      (node (ref "R301") (pin "1") (pinfunction "1_1") (pintype "passive"))
      (node (ref "R312") (pin "1") (pinfunction "1_1") (pintype "passive"))
      (node (ref "R324") (pin "1") (pinfunction "1_1") (pintype "passive"))
      (node (ref "R335") (pin "1") (pinfunction "1_1") (pintype "passive"))
      (node (ref "R347") (pin "1") (pinfunction "1_1") (pintype "passive"))
      (node (ref "R358") (pin "1") (pinfunction "1_1") (pintype "passive"))
      (node (ref "R47") (pin "1") (pinfunction "1_1") (pintype "passive"))
      (node (ref "R59") (pin "1") (pinfunction "1_1") (pintype "passive"))
      (node (ref "R71") (pin "1") (pinfunction "1_1") (pintype "passive"))
      (node (ref "R82") (pin "1") (pinfunction "1_1") (pintype "passive"))
      (node (ref "R94") (pin "1") (pinfunction "1_1") (pintype "passive"))
      (node (ref "X1") (pin "2") (pinfunction "KL_2") (pintype "passive"))
      (node (ref "X11") (pin "2") (pinfunction "KL_2") (pintype "passive"))
      (node (ref "X13") (pin "2") (pinfunction "KL_2") (pintype "passive"))
      (node (ref "X15") (pin "2") (pinfunction "KL_2") (pintype "passive"))
      (node (ref "X17") (pin "2") (pinfunction "KL_2") (pintype "passive"))
      (node (ref "X25") (pin "2") (pinfunction "KL_2") (pintype "passive"))
      (node (ref "X27") (pin "2") (pinfunction "KL_2") (pintype "passive"))
      (node (ref "X29") (pin "2") (pinfunction "KL_2") (pintype "passive"))
      (node (ref "X31") (pin "2") (pinfunction "KL_2") (pintype "passive"))
      (node (ref "X5") (pin "2") (pinfunction "KL_2") (pintype "passive"))
      (node (ref "X7") (pin "2") (pinfunction "KL_2") (pintype "passive"))
      (node (ref "X9") (pin "2") (pinfunction "KL_2") (pintype "passive"))
    )
    (net (code "4") (name "Net-(C2-Pad2)") (class "Default")
      (node (ref "C2") (pin "2") (pinfunction "2_2") (pintype "passive"))
      (node (ref "JP1") (pin "3") (pinfunction "3_3") (pintype "passive"))
      (node (ref "R14") (pin "2") (pinfunction "2_2") (pintype "passive"))
      (node (ref "R15") (pin "2") (pinfunction "2_2") (pintype "passive"))
      (node (ref "R45") (pin "2") (pinfunction "2_2") (pintype "passive"))
      (node (ref "R53") (pin "2") (pinfunction "2_2") (pintype "passive"))
    )
    (net (code "5") (name "Net-(C6-Pad2)") (class "Default")
      (node (ref "C6") (pin "2") (pinfunction "2_2") (pintype "passive"))
      (node (ref "JP7") (pin "3") (pinfunction "3_3") (pintype "passive"))
      (node (ref "R57") (pin "2") (pinfunction "2_2") (pintype "passive"))
      (node (ref "R58") (pin "2") (pinfunction "2_2") (pintype "passive"))
      (node (ref "R68") (pin "2") (pinfunction "2_2") (pintype "passive"))
      (node (ref "R69") (pin "2") (pinfunction "2_2") (pintype "passive"))
    )
    (net (code "6") (name "Net-(C8-Pad2)") (class "Default")
      (node (ref "C8") (pin "2") (pinfunction "2_2") (pintype "passive"))
      (node (ref "JP10") (pin "3") (pinfunction "3_3") (pintype "passive"))
      (node (ref "R80") (pin "2") (pinfunction "2_2") (pintype "passive"))
      (node (ref "R81") (pin "2") (pinfunction "2_2") (pintype "passive"))
      (node (ref "R91") (pin "2") (pinfunction "2_2") (pintype "passive"))
      (node (ref "R92") (pin "2") (pinfunction "2_2") (pintype "passive"))
    )
    (net (code "7") (name "Net-(C10-Pad2)") (class "Default")
      (node (ref "C10") (pin "2") (pinfunction "2_2") (pintype "passive"))
      (node (ref "JP13") (pin "3") (pinfunction "3_3") (pintype "passive"))
      (node (ref "R103") (pin "2") (pinfunction "2_2") (pintype "passive"))
      (node (ref "R104") (pin "2") (pinfunction "2_2") (pintype "passive"))
      (node (ref "R114") (pin "2") (pinfunction "2_2") (pintype "passive"))
      (node (ref "R115") (pin "2") (pinfunction "2_2") (pintype "passive"))
    )
    (net (code "8") (name "Net-(C12-Pad2)") (class "Default")
      (node (ref "C12") (pin "2") (pinfunction "2_2") (pintype "passive"))
      (node (ref "JP16") (pin "3") (pinfunction "3_3") (pintype "passive"))
      (node (ref "R126") (pin "2") (pinfunction "2_2") (pintype "passive"))
      (node (ref "R127") (pin "2") (pinfunction "2_2") (pintype "passive"))
      (node (ref "R137") (pin "2") (pinfunction "2_2") (pintype "passive"))
      (node (ref "R138") (pin "2") (pinfunction "2_2") (pintype "passive"))
    )
    (net (code "9") (name "Net-(C14-Pad2)") (class "Default")
      (node (ref "C14") (pin "2") (pinfunction "2_2") (pintype "passive"))
      (node (ref "JP19") (pin "3") (pinfunction "3_3") (pintype "passive"))
      (node (ref "R149") (pin "2") (pinfunction "2_2") (pintype "passive"))
      (node (ref "R150") (pin "2") (pinfunction "2_2") (pintype "passive"))
      (node (ref "R160") (pin "2") (pinfunction "2_2") (pintype "passive"))
      (node (ref "R161") (pin "2") (pinfunction "2_2") (pintype "passive"))
    )
    (net (code "10") (name "Net-(C16-Pad2)") (class "Default")
      (node (ref "C16") (pin "2") (pinfunction "2_2") (pintype "passive"))
      (node (ref "JP22") (pin "3") (pinfunction "3_3") (pintype "passive"))
      (node (ref "R172") (pin "2") (pinfunction "2_2") (pintype "passive"))
      (node (ref "R173") (pin "2") (pinfunction "2_2") (pintype "passive"))
      (node (ref "R183") (pin "2") (pinfunction "2_2") (pintype "passive"))
      (node (ref "R184") (pin "2") (pinfunction "2_2") (pintype "passive"))
    )
    (net (code "11") (name "Net-(C18-Pad2)") (class "Default")
      (node (ref "C18") (pin "2") (pinfunction "2_2") (pintype "passive"))
      (node (ref "JP25") (pin "3") (pinfunction "3_3") (pintype "passive"))
      (node (ref "R195") (pin "2") (pinfunction "2_2") (pintype "passive"))
      (node (ref "R196") (pin "2") (pinfunction "2_2") (pintype "passive"))
      (node (ref "R206") (pin "2") (pinfunction "2_2") (pintype "passive"))
      (node (ref "R207") (pin "2") (pinfunction "2_2") (pintype "passive"))
    )
    (net (code "12") (name "Net-(C26-Pad2)") (class "Default")
      (node (ref "C26") (pin "2") (pinfunction "2_2") (pintype "passive"))
      (node (ref "JP37") (pin "3") (pinfunction "3_3") (pintype "passive"))
      (node (ref "R287") (pin "2") (pinfunction "2_2") (pintype "passive"))
      (node (ref "R288") (pin "2") (pinfunction "2_2") (pintype "passive"))
      (node (ref "R298") (pin "2") (pinfunction "2_2") (pintype "passive"))
      (node (ref "R299") (pin "2") (pinfunction "2_2") (pintype "passive"))
    )
    (net (code "13") (name "Net-(C28-Pad2)") (class "Default")
      (node (ref "C28") (pin "2") (pinfunction "2_2") (pintype "passive"))
      (node (ref "JP40") (pin "3") (pinfunction "3_3") (pintype "passive"))
      (node (ref "R310") (pin "2") (pinfunction "2_2") (pintype "passive"))
      (node (ref "R311") (pin "2") (pinfunction "2_2") (pintype "passive"))
      (node (ref "R321") (pin "2") (pinfunction "2_2") (pintype "passive"))
      (node (ref "R322") (pin "2") (pinfunction "2_2") (pintype "passive"))
    )
    (net (code "14") (name "Net-(C30-Pad2)") (class "Default")
      (node (ref "C30") (pin "2") (pinfunction "2_2") (pintype "passive"))
      (node (ref "JP43") (pin "3") (pinfunction "3_3") (pintype "passive"))
      (node (ref "R333") (pin "2") (pinfunction "2_2") (pintype "passive"))
      (node (ref "R334") (pin "2") (pinfunction "2_2") (pintype "passive"))
      (node (ref "R344") (pin "2") (pinfunction "2_2") (pintype "passive"))
      (node (ref "R345") (pin "2") (pinfunction "2_2") (pintype "passive"))
    )
    (net (code "15") (name "Net-(C32-Pad2)") (class "Default")
      (node (ref "C32") (pin "2") (pinfunction "2_2") (pintype "passive"))
      (node (ref "JP46") (pin "3") (pinfunction "3_3") (pintype "passive"))
      (node (ref "R356") (pin "2") (pinfunction "2_2") (pintype "passive"))
      (node (ref "R357") (pin "2") (pinfunction "2_2") (pintype "passive"))
      (node (ref "R367") (pin "2") (pinfunction "2_2") (pintype "passive"))
      (node (ref "R368") (pin "2") (pinfunction "2_2") (pintype "passive"))
    )
    (net (code "16") (name "Net-(LED1-PadA)") (class "Default")
      (node (ref "LED1") (pin "A") (pinfunction "A_A") (pintype "passive"))
      (node (ref "R1") (pin "2") (pinfunction "2_2") (pintype "passive"))
    )
    (net (code "17") (name "Net-(LED3-PadA)") (class "Default")
      (node (ref "LED3") (pin "A") (pinfunction "A_A") (pintype "passive"))
      (node (ref "R46") (pin "2") (pinfunction "2_2") (pintype "passive"))
    )
    (net (code "18") (name "Net-(LED4-PadA)") (class "Default")
      (node (ref "LED4") (pin "A") (pinfunction "A_A") (pintype "passive"))
      (node (ref "R70") (pin "2") (pinfunction "2_2") (pintype "passive"))
    )
    (net (code "19") (name "Net-(LED5-PadA)") (class "Default")
      (node (ref "LED5") (pin "A") (pinfunction "A_A") (pintype "passive"))
      (node (ref "R93") (pin "2") (pinfunction "2_2") (pintype "passive"))
    )
    (net (code "20") (name "Net-(LED6-PadA)") (class "Default")
      (node (ref "LED6") (pin "A") (pinfunction "A_A") (pintype "passive"))
      (node (ref "R116") (pin "2") (pinfunction "2_2") (pintype "passive"))
    )
    (net (code "21") (name "Net-(LED7-PadA)") (class "Default")
      (node (ref "LED7") (pin "A") (pinfunction "A_A") (pintype "passive"))
      (node (ref "R139") (pin "2") (pinfunction "2_2") (pintype "passive"))
    )
    (net (code "22") (name "Net-(LED8-PadA)") (class "Default")
      (node (ref "LED8") (pin "A") (pinfunction "A_A") (pintype "passive"))
      (node (ref "R162") (pin "2") (pinfunction "2_2") (pintype "passive"))
    )
    (net (code "23") (name "Net-(LED9-PadA)") (class "Default")
      (node (ref "LED9") (pin "A") (pinfunction "A_A") (pintype "passive"))
      (node (ref "R185") (pin "2") (pinfunction "2_2") (pintype "passive"))
    )
    (net (code "24") (name "Net-(LED13-PadA)") (class "Default")
      (node (ref "LED13") (pin "A") (pinfunction "A_A") (pintype "passive"))
      (node (ref "R277") (pin "2") (pinfunction "2_2") (pintype "passive"))
    )
    (net (code "25") (name "Net-(LED14-PadA)") (class "Default")
      (node (ref "LED14") (pin "A") (pinfunction "A_A") (pintype "passive"))
      (node (ref "R300") (pin "2") (pinfunction "2_2") (pintype "passive"))
    )
    (net (code "26") (name "Net-(LED15-PadA)") (class "Default")
      (node (ref "LED15") (pin "A") (pinfunction "A_A") (pintype "passive"))
      (node (ref "R323") (pin "2") (pinfunction "2_2") (pintype "passive"))
    )
    (net (code "27") (name "Net-(LED16-PadA)") (class "Default")
      (node (ref "LED16") (pin "A") (pinfunction "A_A") (pintype "passive"))
      (node (ref "R346") (pin "2") (pinfunction "2_2") (pintype "passive"))
    )
    (net (code "28") (name "Net-(R2-Pad2)") (class "Default")
      (node (ref "R2") (pin "2") (pinfunction "2_2") (pintype "passive"))
      (node (ref "R4") (pin "1") (pinfunction "1_1") (pintype "passive"))
    )
    (net (code "29") (name "Net-(R3-Pad2)") (class "Default")
      (node (ref "R3") (pin "2") (pinfunction "2_2") (pintype "passive"))
      (node (ref "R8") (pin "1") (pinfunction "1_1") (pintype "passive"))
    )
    (net (code "30") (name "Net-(R4-Pad2)") (class "Default")
      (node (ref "R4") (pin "2") (pinfunction "2_2") (pintype "passive"))
      (node (ref "R5") (pin "1") (pinfunction "1_1") (pintype "passive"))
    )
    (net (code "31") (name "Net-(R5-Pad2)") (class "Default")
      (node (ref "R5") (pin "2") (pinfunction "2_2") (pintype "passive"))
      (node (ref "R6") (pin "1") (pinfunction "1_1") (pintype "passive"))
    )
    (net (code "32") (name "Net-(R6-Pad2)") (class "Default")
      (node (ref "R6") (pin "2") (pinfunction "2_2") (pintype "passive"))
      (node (ref "R7") (pin "1") (pinfunction "1_1") (pintype "passive"))
    )
    (net (code "33") (name "Net-(R7-Pad2)") (class "Default")
      (node (ref "R7") (pin "2") (pinfunction "2_2") (pintype "passive"))
      (node (ref "R9") (pin "1") (pinfunction "1_1") (pintype "passive"))
    )
    (net (code "34") (name "Net-(R10-Pad1)") (class "Default")
      (node (ref "R10") (pin "1") (pinfunction "1_1") (pintype "passive"))
      (node (ref "R9") (pin "2") (pinfunction "2_2") (pintype "passive"))
    )
    (net (code "35") (name "Net-(R10-Pad2)") (class "Default")
      (node (ref "R10") (pin "2") (pinfunction "2_2") (pintype "passive"))
      (node (ref "R11") (pin "1") (pinfunction "1_1") (pintype "passive"))
    )
    (net (code "36") (name "Net-(R11-Pad2)") (class "Default")
      (node (ref "R11") (pin "2") (pinfunction "2_2") (pintype "passive"))
      (node (ref "R12") (pin "1") (pinfunction "1_1") (pintype "passive"))
    )
    (net (code "37") (name "Net-(R12-Pad2)") (class "Default")
      (node (ref "R12") (pin "2") (pinfunction "2_2") (pintype "passive"))
      (node (ref "R14") (pin "1") (pinfunction "1_1") (pintype "passive"))
    )
    (net (code "38") (name "Net-(R13-Pad1)") (class "Default")
      (node (ref "R13") (pin "1") (pinfunction "1_1") (pintype "passive"))
      (node (ref "R8") (pin "2") (pinfunction "2_2") (pintype "passive"))
    )
    (net (code "39") (name "Net-(R13-Pad2)") (class "Default")
      (node (ref "R13") (pin "2") (pinfunction "2_2") (pintype "passive"))
      (node (ref "R18") (pin "1") (pinfunction "1_1") (pintype "passive"))
    )
    (net (code "40") (name "Net-(R18-Pad2)") (class "Default")
      (node (ref "R18") (pin "2") (pinfunction "2_2") (pintype "passive"))
      (node (ref "R23") (pin "1") (pinfunction "1_1") (pintype "passive"))
    )
    (net (code "41") (name "Net-(R23-Pad2)") (class "Default")
      (node (ref "R23") (pin "2") (pinfunction "2_2") (pintype "passive"))
      (node (ref "R28") (pin "1") (pinfunction "1_1") (pintype "passive"))
    )
    (net (code "42") (name "Net-(R28-Pad2)") (class "Default")
      (node (ref "R28") (pin "2") (pinfunction "2_2") (pintype "passive"))
      (node (ref "R33") (pin "1") (pinfunction "1_1") (pintype "passive"))
    )
    (net (code "43") (name "Net-(R33-Pad2)") (class "Default")
      (node (ref "R33") (pin "2") (pinfunction "2_2") (pintype "passive"))
      (node (ref "R38") (pin "1") (pinfunction "1_1") (pintype "passive"))
    )
    (net (code "44") (name "Net-(R38-Pad2)") (class "Default")
      (node (ref "R38") (pin "2") (pinfunction "2_2") (pintype "passive"))
      (node (ref "R43") (pin "1") (pinfunction "1_1") (pintype "passive"))
    )
    (net (code "45") (name "Net-(R43-Pad2)") (class "Default")
      (node (ref "R43") (pin "2") (pinfunction "2_2") (pintype "passive"))
      (node (ref "R45") (pin "1") (pinfunction "1_1") (pintype "passive"))
    )
    (net (code "46") (name "Net-(R47-Pad2)") (class "Default")
      (node (ref "R47") (pin "2") (pinfunction "2_2") (pintype "passive"))
      (node (ref "R48") (pin "1") (pinfunction "1_1") (pintype "passive"))
    )
    (net (code "47") (name "Net-(R48-Pad2)") (class "Default")
      (node (ref "R48") (pin "2") (pinfunction "2_2") (pintype "passive"))
      (node (ref "R49") (pin "1") (pinfunction "1_1") (pintype "passive"))
    )
    (net (code "48") (name "Net-(R49-Pad2)") (class "Default")
      (node (ref "R49") (pin "2") (pinfunction "2_2") (pintype "passive"))
      (node (ref "R50") (pin "1") (pinfunction "1_1") (pintype "passive"))
    )
    (net (code "49") (name "Net-(R50-Pad2)") (class "Default")
      (node (ref "R50") (pin "2") (pinfunction "2_2") (pintype "passive"))
      (node (ref "R51") (pin "1") (pinfunction "1_1") (pintype "passive"))
    )
    (net (code "50") (name "Net-(R51-Pad2)") (class "Default")
      (node (ref "R51") (pin "2") (pinfunction "2_2") (pintype "passive"))
      (node (ref "R52") (pin "1") (pinfunction "1_1") (pintype "passive"))
    )
    (net (code "51") (name "Net-(R52-Pad2)") (class "Default")
      (node (ref "R52") (pin "2") (pinfunction "2_2") (pintype "passive"))
      (node (ref "R54") (pin "1") (pinfunction "1_1") (pintype "passive"))
    )
    (net (code "52") (name "Net-(R54-Pad2)") (class "Default")
      (node (ref "R54") (pin "2") (pinfunction "2_2") (pintype "passive"))
      (node (ref "R55") (pin "1") (pinfunction "1_1") (pintype "passive"))
    )
    (net (code "53") (name "Net-(R55-Pad2)") (class "Default")
      (node (ref "R55") (pin "2") (pinfunction "2_2") (pintype "passive"))
      (node (ref "R56") (pin "1") (pinfunction "1_1") (pintype "passive"))
    )
    (net (code "54") (name "Net-(R56-Pad2)") (class "Default")
      (node (ref "R56") (pin "2") (pinfunction "2_2") (pintype "passive"))
      (node (ref "R57") (pin "1") (pinfunction "1_1") (pintype "passive"))
    )
    (net (code "55") (name "Net-(R59-Pad2)") (class "Default")
      (node (ref "R59") (pin "2") (pinfunction "2_2") (pintype "passive"))
      (node (ref "R60") (pin "1") (pinfunction "1_1") (pintype "passive"))
    )
    (net (code "56") (name "Net-(R60-Pad2)") (class "Default")
      (node (ref "R60") (pin "2") (pinfunction "2_2") (pintype "passive"))
      (node (ref "R61") (pin "1") (pinfunction "1_1") (pintype "passive"))
    )
    (net (code "57") (name "Net-(R61-Pad2)") (class "Default")
      (node (ref "R61") (pin "2") (pinfunction "2_2") (pintype "passive"))
      (node (ref "R62") (pin "1") (pinfunction "1_1") (pintype "passive"))
    )
    (net (code "58") (name "Net-(R62-Pad2)") (class "Default")
      (node (ref "R62") (pin "2") (pinfunction "2_2") (pintype "passive"))
      (node (ref "R63") (pin "1") (pinfunction "1_1") (pintype "passive"))
    )
    (net (code "59") (name "Net-(R63-Pad2)") (class "Default")
      (node (ref "R63") (pin "2") (pinfunction "2_2") (pintype "passive"))
      (node (ref "R64") (pin "1") (pinfunction "1_1") (pintype "passive"))
    )
    (net (code "60") (name "Net-(R64-Pad2)") (class "Default")
      (node (ref "R64") (pin "2") (pinfunction "2_2") (pintype "passive"))
      (node (ref "R65") (pin "1") (pinfunction "1_1") (pintype "passive"))
    )
    (net (code "61") (name "Net-(R65-Pad2)") (class "Default")
      (node (ref "R65") (pin "2") (pinfunction "2_2") (pintype "passive"))
      (node (ref "R66") (pin "1") (pinfunction "1_1") (pintype "passive"))
    )
    (net (code "62") (name "Net-(R66-Pad2)") (class "Default")
      (node (ref "R66") (pin "2") (pinfunction "2_2") (pintype "passive"))
      (node (ref "R67") (pin "1") (pinfunction "1_1") (pintype "passive"))
    )
    (net (code "63") (name "Net-(R67-Pad2)") (class "Default")
      (node (ref "R67") (pin "2") (pinfunction "2_2") (pintype "passive"))
      (node (ref "R68") (pin "1") (pinfunction "1_1") (pintype "passive"))
    )
    (net (code "64") (name "Net-(R71-Pad2)") (class "Default")
      (node (ref "R71") (pin "2") (pinfunction "2_2") (pintype "passive"))
      (node (ref "R72") (pin "1") (pinfunction "1_1") (pintype "passive"))
    )
    (net (code "65") (name "Net-(R72-Pad2)") (class "Default")
      (node (ref "R72") (pin "2") (pinfunction "2_2") (pintype "passive"))
      (node (ref "R73") (pin "1") (pinfunction "1_1") (pintype "passive"))
    )
    (net (code "66") (name "Net-(R73-Pad2)") (class "Default")
      (node (ref "R73") (pin "2") (pinfunction "2_2") (pintype "passive"))
      (node (ref "R74") (pin "1") (pinfunction "1_1") (pintype "passive"))
    )
    (net (code "67") (name "Net-(R74-Pad2)") (class "Default")
      (node (ref "R74") (pin "2") (pinfunction "2_2") (pintype "passive"))
      (node (ref "R75") (pin "1") (pinfunction "1_1") (pintype "passive"))
    )
    (net (code "68") (name "Net-(R75-Pad2)") (class "Default")
      (node (ref "R75") (pin "2") (pinfunction "2_2") (pintype "passive"))
      (node (ref "R76") (pin "1") (pinfunction "1_1") (pintype "passive"))
    )
    (net (code "69") (name "Net-(R76-Pad2)") (class "Default")
      (node (ref "R76") (pin "2") (pinfunction "2_2") (pintype "passive"))
      (node (ref "R77") (pin "1") (pinfunction "1_1") (pintype "passive"))
    )
    (net (code "70") (name "Net-(R77-Pad2)") (class "Default")
      (node (ref "R77") (pin "2") (pinfunction "2_2") (pintype "passive"))
      (node (ref "R78") (pin "1") (pinfunction "1_1") (pintype "passive"))
    )
    (net (code "71") (name "Net-(R78-Pad2)") (class "Default")
      (node (ref "R78") (pin "2") (pinfunction "2_2") (pintype "passive"))
      (node (ref "R79") (pin "1") (pinfunction "1_1") (pintype "passive"))
    )
    (net (code "72") (name "Net-(R79-Pad2)") (class "Default")
      (node (ref "R79") (pin "2") (pinfunction "2_2") (pintype "passive"))
      (node (ref "R80") (pin "1") (pinfunction "1_1") (pintype "passive"))
    )
    (net (code "73") (name "Net-(R82-Pad2)") (class "Default")
      (node (ref "R82") (pin "2") (pinfunction "2_2") (pintype "passive"))
      (node (ref "R83") (pin "1") (pinfunction "1_1") (pintype "passive"))
    )
    (net (code "74") (name "Net-(R83-Pad2)") (class "Default")
      (node (ref "R83") (pin "2") (pinfunction "2_2") (pintype "passive"))
      (node (ref "R84") (pin "1") (pinfunction "1_1") (pintype "passive"))
    )
    (net (code "75") (name "Net-(R84-Pad2)") (class "Default")
      (node (ref "R84") (pin "2") (pinfunction "2_2") (pintype "passive"))
      (node (ref "R85") (pin "1") (pinfunction "1_1") (pintype "passive"))
    )
    (net (code "76") (name "Net-(R85-Pad2)") (class "Default")
      (node (ref "R85") (pin "2") (pinfunction "2_2") (pintype "passive"))
      (node (ref "R86") (pin "1") (pinfunction "1_1") (pintype "passive"))
    )
    (net (code "77") (name "Net-(R86-Pad2)") (class "Default")
      (node (ref "R86") (pin "2") (pinfunction "2_2") (pintype "passive"))
      (node (ref "R87") (pin "1") (pinfunction "1_1") (pintype "passive"))
    )
    (net (code "78") (name "Net-(R87-Pad2)") (class "Default")
      (node (ref "R87") (pin "2") (pinfunction "2_2") (pintype "passive"))
      (node (ref "R88") (pin "1") (pinfunction "1_1") (pintype "passive"))
    )
    (net (code "79") (name "Net-(R88-Pad2)") (class "Default")
      (node (ref "R88") (pin "2") (pinfunction "2_2") (pintype "passive"))
      (node (ref "R89") (pin "1") (pinfunction "1_1") (pintype "passive"))
    )
    (net (code "80") (name "Net-(R89-Pad2)") (class "Default")
      (node (ref "R89") (pin "2") (pinfunction "2_2") (pintype "passive"))
      (node (ref "R90") (pin "1") (pinfunction "1_1") (pintype "passive"))
    )
    (net (code "81") (name "Net-(R90-Pad2)") (class "Default")
      (node (ref "R90") (pin "2") (pinfunction "2_2") (pintype "passive"))
      (node (ref "R91") (pin "1") (pinfunction "1_1") (pintype "passive"))
    )
    (net (code "82") (name "Net-(R94-Pad2)") (class "Default")
      (node (ref "R94") (pin "2") (pinfunction "2_2") (pintype "passive"))
      (node (ref "R95") (pin "1") (pinfunction "1_1") (pintype "passive"))
    )
    (net (code "83") (name "Net-(R95-Pad2)") (class "Default")
      (node (ref "R95") (pin "2") (pinfunction "2_2") (pintype "passive"))
      (node (ref "R96") (pin "1") (pinfunction "1_1") (pintype "passive"))
    )
    (net (code "84") (name "Net-(R96-Pad2)") (class "Default")
      (node (ref "R96") (pin "2") (pinfunction "2_2") (pintype "passive"))
      (node (ref "R97") (pin "1") (pinfunction "1_1") (pintype "passive"))
    )
    (net (code "85") (name "Net-(R97-Pad2)") (class "Default")
      (node (ref "R97") (pin "2") (pinfunction "2_2") (pintype "passive"))
      (node (ref "R98") (pin "1") (pinfunction "1_1") (pintype "passive"))
    )
    (net (code "86") (name "Net-(R98-Pad2)") (class "Default")
      (node (ref "R98") (pin "2") (pinfunction "2_2") (pintype "passive"))
      (node (ref "R99") (pin "1") (pinfunction "1_1") (pintype "passive"))
    )
    (net (code "87") (name "Net-(R100-Pad1)") (class "Default")
      (node (ref "R100") (pin "1") (pinfunction "1_1") (pintype "passive"))
      (node (ref "R99") (pin "2") (pinfunction "2_2") (pintype "passive"))
    )
    (net (code "88") (name "Net-(R100-Pad2)") (class "Default")
      (node (ref "R100") (pin "2") (pinfunction "2_2") (pintype "passive"))
      (node (ref "R101") (pin "1") (pinfunction "1_1") (pintype "passive"))
    )
    (net (code "89") (name "Net-(R101-Pad2)") (class "Default")
      (node (ref "R101") (pin "2") (pinfunction "2_2") (pintype "passive"))
      (node (ref "R102") (pin "1") (pinfunction "1_1") (pintype "passive"))
    )
    (net (code "90") (name "Net-(R102-Pad2)") (class "Default")
      (node (ref "R102") (pin "2") (pinfunction "2_2") (pintype "passive"))
      (node (ref "R103") (pin "1") (pinfunction "1_1") (pintype "passive"))
    )
    (net (code "91") (name "Net-(R105-Pad2)") (class "Default")
      (node (ref "R105") (pin "2") (pinfunction "2_2") (pintype "passive"))
      (node (ref "R106") (pin "1") (pinfunction "1_1") (pintype "passive"))
    )
    (net (code "92") (name "Net-(R106-Pad2)") (class "Default")
      (node (ref "R106") (pin "2") (pinfunction "2_2") (pintype "passive"))
      (node (ref "R107") (pin "1") (pinfunction "1_1") (pintype "passive"))
    )
    (net (code "93") (name "Net-(R107-Pad2)") (class "Default")
      (node (ref "R107") (pin "2") (pinfunction "2_2") (pintype "passive"))
      (node (ref "R108") (pin "1") (pinfunction "1_1") (pintype "passive"))
    )
    (net (code "94") (name "Net-(R108-Pad2)") (class "Default")
      (node (ref "R108") (pin "2") (pinfunction "2_2") (pintype "passive"))
      (node (ref "R109") (pin "1") (pinfunction "1_1") (pintype "passive"))
    )
    (net (code "95") (name "Net-(R109-Pad2)") (class "Default")
      (node (ref "R109") (pin "2") (pinfunction "2_2") (pintype "passive"))
      (node (ref "R110") (pin "1") (pinfunction "1_1") (pintype "passive"))
    )
    (net (code "96") (name "Net-(R110-Pad2)") (class "Default")
      (node (ref "R110") (pin "2") (pinfunction "2_2") (pintype "passive"))
      (node (ref "R111") (pin "1") (pinfunction "1_1") (pintype "passive"))
    )
    (net (code "97") (name "Net-(R111-Pad2)") (class "Default")
      (node (ref "R111") (pin "2") (pinfunction "2_2") (pintype "passive"))
      (node (ref "R112") (pin "1") (pinfunction "1_1") (pintype "passive"))
    )
    (net (code "98") (name "Net-(R112-Pad2)") (class "Default")
      (node (ref "R112") (pin "2") (pinfunction "2_2") (pintype "passive"))
      (node (ref "R113") (pin "1") (pinfunction "1_1") (pintype "passive"))
    )
    (net (code "99") (name "Net-(R113-Pad2)") (class "Default")
      (node (ref "R113") (pin "2") (pinfunction "2_2") (pintype "passive"))
      (node (ref "R114") (pin "1") (pinfunction "1_1") (pintype "passive"))
    )
    (net (code "100") (name "Net-(R117-Pad2)") (class "Default")
      (node (ref "R117") (pin "2") (pinfunction "2_2") (pintype "passive"))
      (node (ref "R118") (pin "1") (pinfunction "1_1") (pintype "passive"))
    )
    (net (code "101") (name "Net-(R118-Pad2)") (class "Default")
      (node (ref "R118") (pin "2") (pinfunction "2_2") (pintype "passive"))
      (node (ref "R119") (pin "1") (pinfunction "1_1") (pintype "passive"))
    )
    (net (code "102") (name "Net-(R119-Pad2)") (class "Default")
      (node (ref "R119") (pin "2") (pinfunction "2_2") (pintype "passive"))
      (node (ref "R120") (pin "1") (pinfunction "1_1") (pintype "passive"))
    )
    (net (code "103") (name "Net-(R120-Pad2)") (class "Default")
      (node (ref "R120") (pin "2") (pinfunction "2_2") (pintype "passive"))
      (node (ref "R121") (pin "1") (pinfunction "1_1") (pintype "passive"))
    )
    (net (code "104") (name "Net-(R121-Pad2)") (class "Default")
      (node (ref "R121") (pin "2") (pinfunction "2_2") (pintype "passive"))
      (node (ref "R122") (pin "1") (pinfunction "1_1") (pintype "passive"))
    )
    (net (code "105") (name "Net-(R122-Pad2)") (class "Default")
      (node (ref "R122") (pin "2") (pinfunction "2_2") (pintype "passive"))
      (node (ref "R123") (pin "1") (pinfunction "1_1") (pintype "passive"))
    )
    (net (code "106") (name "Net-(R123-Pad2)") (class "Default")
      (node (ref "R123") (pin "2") (pinfunction "2_2") (pintype "passive"))
      (node (ref "R124") (pin "1") (pinfunction "1_1") (pintype "passive"))
    )
    (net (code "107") (name "Net-(R124-Pad2)") (class "Default")
      (node (ref "R124") (pin "2") (pinfunction "2_2") (pintype "passive"))
      (node (ref "R125") (pin "1") (pinfunction "1_1") (pintype "passive"))
    )
    (net (code "108") (name "Net-(R125-Pad2)") (class "Default")
      (node (ref "R125") (pin "2") (pinfunction "2_2") (pintype "passive"))
      (node (ref "R126") (pin "1") (pinfunction "1_1") (pintype "passive"))
    )
    (net (code "109") (name "Net-(R128-Pad2)") (class "Default")
      (node (ref "R128") (pin "2") (pinfunction "2_2") (pintype "passive"))
      (node (ref "R129") (pin "1") (pinfunction "1_1") (pintype "passive"))
    )
    (net (code "110") (name "Net-(R129-Pad2)") (class "Default")
      (node (ref "R129") (pin "2") (pinfunction "2_2") (pintype "passive"))
      (node (ref "R130") (pin "1") (pinfunction "1_1") (pintype "passive"))
    )
    (net (code "111") (name "Net-(R130-Pad2)") (class "Default")
      (node (ref "R130") (pin "2") (pinfunction "2_2") (pintype "passive"))
      (node (ref "R131") (pin "1") (pinfunction "1_1") (pintype "passive"))
    )
    (net (code "112") (name "Net-(R131-Pad2)") (class "Default")
      (node (ref "R131") (pin "2") (pinfunction "2_2") (pintype "passive"))
      (node (ref "R132") (pin "1") (pinfunction "1_1") (pintype "passive"))
    )
    (net (code "113") (name "Net-(R132-Pad2)") (class "Default")
      (node (ref "R132") (pin "2") (pinfunction "2_2") (pintype "passive"))
      (node (ref "R133") (pin "1") (pinfunction "1_1") (pintype "passive"))
    )
    (net (code "114") (name "Net-(R133-Pad2)") (class "Default")
      (node (ref "R133") (pin "2") (pinfunction "2_2") (pintype "passive"))
      (node (ref "R134") (pin "1") (pinfunction "1_1") (pintype "passive"))
    )
    (net (code "115") (name "Net-(R134-Pad2)") (class "Default")
      (node (ref "R134") (pin "2") (pinfunction "2_2") (pintype "passive"))
      (node (ref "R135") (pin "1") (pinfunction "1_1") (pintype "passive"))
    )
    (net (code "116") (name "Net-(R135-Pad2)") (class "Default")
      (node (ref "R135") (pin "2") (pinfunction "2_2") (pintype "passive"))
      (node (ref "R136") (pin "1") (pinfunction "1_1") (pintype "passive"))
    )
    (net (code "117") (name "Net-(R136-Pad2)") (class "Default")
      (node (ref "R136") (pin "2") (pinfunction "2_2") (pintype "passive"))
      (node (ref "R137") (pin "1") (pinfunction "1_1") (pintype "passive"))
    )
    (net (code "118") (name "Net-(R140-Pad2)") (class "Default")
      (node (ref "R140") (pin "2") (pinfunction "2_2") (pintype "passive"))
      (node (ref "R141") (pin "1") (pinfunction "1_1") (pintype "passive"))
    )
    (net (code "119") (name "Net-(R141-Pad2)") (class "Default")
      (node (ref "R141") (pin "2") (pinfunction "2_2") (pintype "passive"))
      (node (ref "R142") (pin "1") (pinfunction "1_1") (pintype "passive"))
    )
    (net (code "120") (name "Net-(R142-Pad2)") (class "Default")
      (node (ref "R142") (pin "2") (pinfunction "2_2") (pintype "passive"))
      (node (ref "R143") (pin "1") (pinfunction "1_1") (pintype "passive"))
    )
    (net (code "121") (name "Net-(R143-Pad2)") (class "Default")
      (node (ref "R143") (pin "2") (pinfunction "2_2") (pintype "passive"))
      (node (ref "R144") (pin "1") (pinfunction "1_1") (pintype "passive"))
    )
    (net (code "122") (name "Net-(R144-Pad2)") (class "Default")
      (node (ref "R144") (pin "2") (pinfunction "2_2") (pintype "passive"))
      (node (ref "R145") (pin "1") (pinfunction "1_1") (pintype "passive"))
    )
    (net (code "123") (name "Net-(R145-Pad2)") (class "Default")
      (node (ref "R145") (pin "2") (pinfunction "2_2") (pintype "passive"))
      (node (ref "R146") (pin "1") (pinfunction "1_1") (pintype "passive"))
    )
    (net (code "124") (name "Net-(R146-Pad2)") (class "Default")
      (node (ref "R146") (pin "2") (pinfunction "2_2") (pintype "passive"))
      (node (ref "R147") (pin "1") (pinfunction "1_1") (pintype "passive"))
    )
    (net (code "125") (name "Net-(R147-Pad2)") (class "Default")
      (node (ref "R147") (pin "2") (pinfunction "2_2") (pintype "passive"))
      (node (ref "R148") (pin "1") (pinfunction "1_1") (pintype "passive"))
    )
    (net (code "126") (name "Net-(R148-Pad2)") (class "Default")
      (node (ref "R148") (pin "2") (pinfunction "2_2") (pintype "passive"))
      (node (ref "R149") (pin "1") (pinfunction "1_1") (pintype "passive"))
    )
    (net (code "127") (name "Net-(R151-Pad2)") (class "Default")
      (node (ref "R151") (pin "2") (pinfunction "2_2") (pintype "passive"))
      (node (ref "R152") (pin "1") (pinfunction "1_1") (pintype "passive"))
    )
    (net (code "128") (name "Net-(R152-Pad2)") (class "Default")
      (node (ref "R152") (pin "2") (pinfunction "2_2") (pintype "passive"))
      (node (ref "R153") (pin "1") (pinfunction "1_1") (pintype "passive"))
    )
    (net (code "129") (name "Net-(R153-Pad2)") (class "Default")
      (node (ref "R153") (pin "2") (pinfunction "2_2") (pintype "passive"))
      (node (ref "R154") (pin "1") (pinfunction "1_1") (pintype "passive"))
    )
    (net (code "130") (name "Net-(R154-Pad2)") (class "Default")
      (node (ref "R154") (pin "2") (pinfunction "2_2") (pintype "passive"))
      (node (ref "R155") (pin "1") (pinfunction "1_1") (pintype "passive"))
    )
    (net (code "131") (name "Net-(R155-Pad2)") (class "Default")
      (node (ref "R155") (pin "2") (pinfunction "2_2") (pintype "passive"))
      (node (ref "R156") (pin "1") (pinfunction "1_1") (pintype "passive"))
    )
    (net (code "132") (name "Net-(R156-Pad2)") (class "Default")
      (node (ref "R156") (pin "2") (pinfunction "2_2") (pintype "passive"))
      (node (ref "R157") (pin "1") (pinfunction "1_1") (pintype "passive"))
    )
    (net (code "133") (name "Net-(R157-Pad2)") (class "Default")
      (node (ref "R157") (pin "2") (pinfunction "2_2") (pintype "passive"))
      (node (ref "R158") (pin "1") (pinfunction "1_1") (pintype "passive"))
    )
    (net (code "134") (name "Net-(R158-Pad2)") (class "Default")
      (node (ref "R158") (pin "2") (pinfunction "2_2") (pintype "passive"))
      (node (ref "R159") (pin "1") (pinfunction "1_1") (pintype "passive"))
    )
    (net (code "135") (name "Net-(R159-Pad2)") (class "Default")
      (node (ref "R159") (pin "2") (pinfunction "2_2") (pintype "passive"))
      (node (ref "R160") (pin "1") (pinfunction "1_1") (pintype "passive"))
    )
    (net (code "136") (name "Net-(R163-Pad2)") (class "Default")
      (node (ref "R163") (pin "2") (pinfunction "2_2") (pintype "passive"))
      (node (ref "R164") (pin "1") (pinfunction "1_1") (pintype "passive"))
    )
    (net (code "137") (name "Net-(R164-Pad2)") (class "Default")
      (node (ref "R164") (pin "2") (pinfunction "2_2") (pintype "passive"))
      (node (ref "R165") (pin "1") (pinfunction "1_1") (pintype "passive"))
    )
    (net (code "138") (name "Net-(R165-Pad2)") (class "Default")
      (node (ref "R165") (pin "2") (pinfunction "2_2") (pintype "passive"))
      (node (ref "R166") (pin "1") (pinfunction "1_1") (pintype "passive"))
    )
    (net (code "139") (name "Net-(R166-Pad2)") (class "Default")
      (node (ref "R166") (pin "2") (pinfunction "2_2") (pintype "passive"))
      (node (ref "R167") (pin "1") (pinfunction "1_1") (pintype "passive"))
    )
    (net (code "140") (name "Net-(R167-Pad2)") (class "Default")
      (node (ref "R167") (pin "2") (pinfunction "2_2") (pintype "passive"))
      (node (ref "R168") (pin "1") (pinfunction "1_1") (pintype "passive"))
    )
    (net (code "141") (name "Net-(R168-Pad2)") (class "Default")
      (node (ref "R168") (pin "2") (pinfunction "2_2") (pintype "passive"))
      (node (ref "R169") (pin "1") (pinfunction "1_1") (pintype "passive"))
    )
    (net (code "142") (name "Net-(R169-Pad2)") (class "Default")
      (node (ref "R169") (pin "2") (pinfunction "2_2") (pintype "passive"))
      (node (ref "R170") (pin "1") (pinfunction "1_1") (pintype "passive"))
    )
    (net (code "143") (name "Net-(R170-Pad2)") (class "Default")
      (node (ref "R170") (pin "2") (pinfunction "2_2") (pintype "passive"))
      (node (ref "R171") (pin "1") (pinfunction "1_1") (pintype "passive"))
    )
    (net (code "144") (name "Net-(R171-Pad2)") (class "Default")
      (node (ref "R171") (pin "2") (pinfunction "2_2") (pintype "passive"))
      (node (ref "R172") (pin "1") (pinfunction "1_1") (pintype "passive"))
    )
    (net (code "145") (name "Net-(R174-Pad2)") (class "Default")
      (node (ref "R174") (pin "2") (pinfunction "2_2") (pintype "passive"))
      (node (ref "R175") (pin "1") (pinfunction "1_1") (pintype "passive"))
    )
    (net (code "146") (name "Net-(R175-Pad2)") (class "Default")
      (node (ref "R175") (pin "2") (pinfunction "2_2") (pintype "passive"))
      (node (ref "R176") (pin "1") (pinfunction "1_1") (pintype "passive"))
    )
    (net (code "147") (name "Net-(R176-Pad2)") (class "Default")
      (node (ref "R176") (pin "2") (pinfunction "2_2") (pintype "passive"))
      (node (ref "R177") (pin "1") (pinfunction "1_1") (pintype "passive"))
    )
    (net (code "148") (name "Net-(R177-Pad2)") (class "Default")
      (node (ref "R177") (pin "2") (pinfunction "2_2") (pintype "passive"))
      (node (ref "R178") (pin "1") (pinfunction "1_1") (pintype "passive"))
    )
    (net (code "149") (name "Net-(R178-Pad2)") (class "Default")
      (node (ref "R178") (pin "2") (pinfunction "2_2") (pintype "passive"))
      (node (ref "R179") (pin "1") (pinfunction "1_1") (pintype "passive"))
    )
    (net (code "150") (name "Net-(R179-Pad2)") (class "Default")
      (node (ref "R179") (pin "2") (pinfunction "2_2") (pintype "passive"))
      (node (ref "R180") (pin "1") (pinfunction "1_1") (pintype "passive"))
    )
    (net (code "151") (name "Net-(R180-Pad2)") (class "Default")
      (node (ref "R180") (pin "2") (pinfunction "2_2") (pintype "passive"))
      (node (ref "R181") (pin "1") (pinfunction "1_1") (pintype "passive"))
    )
    (net (code "152") (name "Net-(R181-Pad2)") (class "Default")
      (node (ref "R181") (pin "2") (pinfunction "2_2") (pintype "passive"))
      (node (ref "R182") (pin "1") (pinfunction "1_1") (pintype "passive"))
    )
    (net (code "153") (name "Net-(R182-Pad2)") (class "Default")
      (node (ref "R182") (pin "2") (pinfunction "2_2") (pintype "passive"))
      (node (ref "R183") (pin "1") (pinfunction "1_1") (pintype "passive"))
    )
    (net (code "154") (name "Net-(R186-Pad2)") (class "Default")
      (node (ref "R186") (pin "2") (pinfunction "2_2") (pintype "passive"))
      (node (ref "R187") (pin "1") (pinfunction "1_1") (pintype "passive"))
    )
    (net (code "155") (name "Net-(R187-Pad2)") (class "Default")
      (node (ref "R187") (pin "2") (pinfunction "2_2") (pintype "passive"))
      (node (ref "R188") (pin "1") (pinfunction "1_1") (pintype "passive"))
    )
    (net (code "156") (name "Net-(R188-Pad2)") (class "Default")
      (node (ref "R188") (pin "2") (pinfunction "2_2") (pintype "passive"))
      (node (ref "R189") (pin "1") (pinfunction "1_1") (pintype "passive"))
    )
    (net (code "157") (name "Net-(R189-Pad2)") (class "Default")
      (node (ref "R189") (pin "2") (pinfunction "2_2") (pintype "passive"))
      (node (ref "R190") (pin "1") (pinfunction "1_1") (pintype "passive"))
    )
    (net (code "158") (name "Net-(R190-Pad2)") (class "Default")
      (node (ref "R190") (pin "2") (pinfunction "2_2") (pintype "passive"))
      (node (ref "R191") (pin "1") (pinfunction "1_1") (pintype "passive"))
    )
    (net (code "159") (name "Net-(R191-Pad2)") (class "Default")
      (node (ref "R191") (pin "2") (pinfunction "2_2") (pintype "passive"))
      (node (ref "R192") (pin "1") (pinfunction "1_1") (pintype "passive"))
    )
    (net (code "160") (name "Net-(R192-Pad2)") (class "Default")
      (node (ref "R192") (pin "2") (pinfunction "2_2") (pintype "passive"))
      (node (ref "R193") (pin "1") (pinfunction "1_1") (pintype "passive"))
    )
    (net (code "161") (name "Net-(R193-Pad2)") (class "Default")
      (node (ref "R193") (pin "2") (pinfunction "2_2") (pintype "passive"))
      (node (ref "R194") (pin "1") (pinfunction "1_1") (pintype "passive"))
    )
    (net (code "162") (name "Net-(R194-Pad2)") (class "Default")
      (node (ref "R194") (pin "2") (pinfunction "2_2") (pintype "passive"))
      (node (ref "R195") (pin "1") (pinfunction "1_1") (pintype "passive"))
    )
    (net (code "163") (name "Net-(R197-Pad2)") (class "Default")
      (node (ref "R197") (pin "2") (pinfunction "2_2") (pintype "passive"))
      (node (ref "R198") (pin "1") (pinfunction "1_1") (pintype "passive"))
    )
    (net (code "164") (name "Net-(R198-Pad2)") (class "Default")
      (node (ref "R198") (pin "2") (pinfunction "2_2") (pintype "passive"))
      (node (ref "R199") (pin "1") (pinfunction "1_1") (pintype "passive"))
    )
    (net (code "165") (name "Net-(R199-Pad2)") (class "Default")
      (node (ref "R199") (pin "2") (pinfunction "2_2") (pintype "passive"))
      (node (ref "R200") (pin "1") (pinfunction "1_1") (pintype "passive"))
    )
    (net (code "166") (name "Net-(R200-Pad2)") (class "Default")
      (node (ref "R200") (pin "2") (pinfunction "2_2") (pintype "passive"))
      (node (ref "R201") (pin "1") (pinfunction "1_1") (pintype "passive"))
    )
    (net (code "167") (name "Net-(R201-Pad2)") (class "Default")
      (node (ref "R201") (pin "2") (pinfunction "2_2") (pintype "passive"))
      (node (ref "R202") (pin "1") (pinfunction "1_1") (pintype "passive"))
    )
    (net (code "168") (name "Net-(R202-Pad2)") (class "Default")
      (node (ref "R202") (pin "2") (pinfunction "2_2") (pintype "passive"))
      (node (ref "R203") (pin "1") (pinfunction "1_1") (pintype "passive"))
    )
    (net (code "169") (name "Net-(R203-Pad2)") (class "Default")
      (node (ref "R203") (pin "2") (pinfunction "2_2") (pintype "passive"))
      (node (ref "R204") (pin "1") (pinfunction "1_1") (pintype "passive"))
    )
    (net (code "170") (name "Net-(R204-Pad2)") (class "Default")
      (node (ref "R204") (pin "2") (pinfunction "2_2") (pintype "passive"))
      (node (ref "R205") (pin "1") (pinfunction "1_1") (pintype "passive"))
    )
    (net (code "171") (name "Net-(R205-Pad2)") (class "Default")
      (node (ref "R205") (pin "2") (pinfunction "2_2") (pintype "passive"))
      (node (ref "R206") (pin "1") (pinfunction "1_1") (pintype "passive"))
    )
    (net (code "172") (name "Net-(R278-Pad2)") (class "Default")
      (node (ref "R278") (pin "2") (pinfunction "2_2") (pintype "passive"))
      (node (ref "R279") (pin "1") (pinfunction "1_1") (pintype "passive"))
    )
    (net (code "173") (name "Net-(R279-Pad2)") (class "Default")
      (node (ref "R279") (pin "2") (pinfunction "2_2") (pintype "passive"))
      (node (ref "R280") (pin "1") (pinfunction "1_1") (pintype "passive"))
    )
    (net (code "174") (name "Net-(R280-Pad2)") (class "Default")
      (node (ref "R280") (pin "2") (pinfunction "2_2") (pintype "passive"))
      (node (ref "R281") (pin "1") (pinfunction "1_1") (pintype "passive"))
    )
    (net (code "175") (name "Net-(R281-Pad2)") (class "Default")
      (node (ref "R281") (pin "2") (pinfunction "2_2") (pintype "passive"))
      (node (ref "R282") (pin "1") (pinfunction "1_1") (pintype "passive"))
    )
    (net (code "176") (name "Net-(R282-Pad2)") (class "Default")
      (node (ref "R282") (pin "2") (pinfunction "2_2") (pintype "passive"))
      (node (ref "R283") (pin "1") (pinfunction "1_1") (pintype "passive"))
    )
    (net (code "177") (name "Net-(R283-Pad2)") (class "Default")
      (node (ref "R283") (pin "2") (pinfunction "2_2") (pintype "passive"))
      (node (ref "R284") (pin "1") (pinfunction "1_1") (pintype "passive"))
    )
    (net (code "178") (name "Net-(R284-Pad2)") (class "Default")
      (node (ref "R284") (pin "2") (pinfunction "2_2") (pintype "passive"))
      (node (ref "R285") (pin "1") (pinfunction "1_1") (pintype "passive"))
    )
    (net (code "179") (name "Net-(R285-Pad2)") (class "Default")
      (node (ref "R285") (pin "2") (pinfunction "2_2") (pintype "passive"))
      (node (ref "R286") (pin "1") (pinfunction "1_1") (pintype "passive"))
    )
    (net (code "180") (name "Net-(R286-Pad2)") (class "Default")
      (node (ref "R286") (pin "2") (pinfunction "2_2") (pintype "passive"))
      (node (ref "R287") (pin "1") (pinfunction "1_1") (pintype "passive"))
    )
    (net (code "181") (name "Net-(R289-Pad2)") (class "Default")
      (node (ref "R289") (pin "2") (pinfunction "2_2") (pintype "passive"))
      (node (ref "R290") (pin "1") (pinfunction "1_1") (pintype "passive"))
    )
    (net (code "182") (name "Net-(R290-Pad2)") (class "Default")
      (node (ref "R290") (pin "2") (pinfunction "2_2") (pintype "passive"))
      (node (ref "R291") (pin "1") (pinfunction "1_1") (pintype "passive"))
    )
    (net (code "183") (name "Net-(R291-Pad2)") (class "Default")
      (node (ref "R291") (pin "2") (pinfunction "2_2") (pintype "passive"))
      (node (ref "R292") (pin "1") (pinfunction "1_1") (pintype "passive"))
    )
    (net (code "184") (name "Net-(R292-Pad2)") (class "Default")
      (node (ref "R292") (pin "2") (pinfunction "2_2") (pintype "passive"))
      (node (ref "R293") (pin "1") (pinfunction "1_1") (pintype "passive"))
    )
    (net (code "185") (name "Net-(R293-Pad2)") (class "Default")
      (node (ref "R293") (pin "2") (pinfunction "2_2") (pintype "passive"))
      (node (ref "R294") (pin "1") (pinfunction "1_1") (pintype "passive"))
    )
    (net (code "186") (name "Net-(R294-Pad2)") (class "Default")
      (node (ref "R294") (pin "2") (pinfunction "2_2") (pintype "passive"))
      (node (ref "R295") (pin "1") (pinfunction "1_1") (pintype "passive"))
    )
    (net (code "187") (name "Net-(R295-Pad2)") (class "Default")
      (node (ref "R295") (pin "2") (pinfunction "2_2") (pintype "passive"))
      (node (ref "R296") (pin "1") (pinfunction "1_1") (pintype "passive"))
    )
    (net (code "188") (name "Net-(R296-Pad2)") (class "Default")
      (node (ref "R296") (pin "2") (pinfunction "2_2") (pintype "passive"))
      (node (ref "R297") (pin "1") (pinfunction "1_1") (pintype "passive"))
    )
    (net (code "189") (name "Net-(R297-Pad2)") (class "Default")
      (node (ref "R297") (pin "2") (pinfunction "2_2") (pintype "passive"))
      (node (ref "R298") (pin "1") (pinfunction "1_1") (pintype "passive"))
    )
    (net (code "190") (name "Net-(R301-Pad2)") (class "Default")
      (node (ref "R301") (pin "2") (pinfunction "2_2") (pintype "passive"))
      (node (ref "R302") (pin "1") (pinfunction "1_1") (pintype "passive"))
    )
    (net (code "191") (name "Net-(R302-Pad2)") (class "Default")
      (node (ref "R302") (pin "2") (pinfunction "2_2") (pintype "passive"))
      (node (ref "R303") (pin "1") (pinfunction "1_1") (pintype "passive"))
    )
    (net (code "192") (name "Net-(R303-Pad2)") (class "Default")
      (node (ref "R303") (pin "2") (pinfunction "2_2") (pintype "passive"))
      (node (ref "R304") (pin "1") (pinfunction "1_1") (pintype "passive"))
    )
    (net (code "193") (name "Net-(R304-Pad2)") (class "Default")
      (node (ref "R304") (pin "2") (pinfunction "2_2") (pintype "passive"))
      (node (ref "R305") (pin "1") (pinfunction "1_1") (pintype "passive"))
    )
    (net (code "194") (name "Net-(R305-Pad2)") (class "Default")
      (node (ref "R305") (pin "2") (pinfunction "2_2") (pintype "passive"))
      (node (ref "R306") (pin "1") (pinfunction "1_1") (pintype "passive"))
    )
    (net (code "195") (name "Net-(R306-Pad2)") (class "Default")
      (node (ref "R306") (pin "2") (pinfunction "2_2") (pintype "passive"))
      (node (ref "R307") (pin "1") (pinfunction "1_1") (pintype "passive"))
    )
    (net (code "196") (name "Net-(R307-Pad2)") (class "Default")
      (node (ref "R307") (pin "2") (pinfunction "2_2") (pintype "passive"))
      (node (ref "R308") (pin "1") (pinfunction "1_1") (pintype "passive"))
    )
    (net (code "197") (name "Net-(R308-Pad2)") (class "Default")
      (node (ref "R308") (pin "2") (pinfunction "2_2") (pintype "passive"))
      (node (ref "R309") (pin "1") (pinfunction "1_1") (pintype "passive"))
    )
    (net (code "198") (name "Net-(R309-Pad2)") (class "Default")
      (node (ref "R309") (pin "2") (pinfunction "2_2") (pintype "passive"))
      (node (ref "R310") (pin "1") (pinfunction "1_1") (pintype "passive"))
    )
    (net (code "199") (name "Net-(R312-Pad2)") (class "Default")
      (node (ref "R312") (pin "2") (pinfunction "2_2") (pintype "passive"))
      (node (ref "R313") (pin "1") (pinfunction "1_1") (pintype "passive"))
    )
    (net (code "200") (name "Net-(R313-Pad2)") (class "Default")
      (node (ref "R313") (pin "2") (pinfunction "2_2") (pintype "passive"))
      (node (ref "R314") (pin "1") (pinfunction "1_1") (pintype "passive"))
    )
    (net (code "201") (name "Net-(R314-Pad2)") (class "Default")
      (node (ref "R314") (pin "2") (pinfunction "2_2") (pintype "passive"))
      (node (ref "R315") (pin "1") (pinfunction "1_1") (pintype "passive"))
    )
    (net (code "202") (name "Net-(R315-Pad2)") (class "Default")
      (node (ref "R315") (pin "2") (pinfunction "2_2") (pintype "passive"))
      (node (ref "R316") (pin "1") (pinfunction "1_1") (pintype "passive"))
    )
    (net (code "203") (name "Net-(R316-Pad2)") (class "Default")
      (node (ref "R316") (pin "2") (pinfunction "2_2") (pintype "passive"))
      (node (ref "R317") (pin "1") (pinfunction "1_1") (pintype "passive"))
    )
    (net (code "204") (name "Net-(R317-Pad2)") (class "Default")
      (node (ref "R317") (pin "2") (pinfunction "2_2") (pintype "passive"))
      (node (ref "R318") (pin "1") (pinfunction "1_1") (pintype "passive"))
    )
    (net (code "205") (name "Net-(R318-Pad2)") (class "Default")
      (node (ref "R318") (pin "2") (pinfunction "2_2") (pintype "passive"))
      (node (ref "R319") (pin "1") (pinfunction "1_1") (pintype "passive"))
    )
    (net (code "206") (name "Net-(R319-Pad2)") (class "Default")
      (node (ref "R319") (pin "2") (pinfunction "2_2") (pintype "passive"))
      (node (ref "R320") (pin "1") (pinfunction "1_1") (pintype "passive"))
    )
    (net (code "207") (name "Net-(R320-Pad2)") (class "Default")
      (node (ref "R320") (pin "2") (pinfunction "2_2") (pintype "passive"))
      (node (ref "R321") (pin "1") (pinfunction "1_1") (pintype "passive"))
    )
    (net (code "208") (name "Net-(R324-Pad2)") (class "Default")
      (node (ref "R324") (pin "2") (pinfunction "2_2") (pintype "passive"))
      (node (ref "R325") (pin "1") (pinfunction "1_1") (pintype "passive"))
    )
    (net (code "209") (name "Net-(R325-Pad2)") (class "Default")
      (node (ref "R325") (pin "2") (pinfunction "2_2") (pintype "passive"))
      (node (ref "R326") (pin "1") (pinfunction "1_1") (pintype "passive"))
    )
    (net (code "210") (name "Net-(R326-Pad2)") (class "Default")
      (node (ref "R326") (pin "2") (pinfunction "2_2") (pintype "passive"))
      (node (ref "R327") (pin "1") (pinfunction "1_1") (pintype "passive"))
    )
    (net (code "211") (name "Net-(R327-Pad2)") (class "Default")
      (node (ref "R327") (pin "2") (pinfunction "2_2") (pintype "passive"))
      (node (ref "R328") (pin "1") (pinfunction "1_1") (pintype "passive"))
    )
    (net (code "212") (name "Net-(R328-Pad2)") (class "Default")
      (node (ref "R328") (pin "2") (pinfunction "2_2") (pintype "passive"))
      (node (ref "R329") (pin "1") (pinfunction "1_1") (pintype "passive"))
    )
    (net (code "213") (name "Net-(R329-Pad2)") (class "Default")
      (node (ref "R329") (pin "2") (pinfunction "2_2") (pintype "passive"))
      (node (ref "R330") (pin "1") (pinfunction "1_1") (pintype "passive"))
    )
    (net (code "214") (name "Net-(R330-Pad2)") (class "Default")
      (node (ref "R330") (pin "2") (pinfunction "2_2") (pintype "passive"))
      (node (ref "R331") (pin "1") (pinfunction "1_1") (pintype "passive"))
    )
    (net (code "215") (name "Net-(R331-Pad2)") (class "Default")
      (node (ref "R331") (pin "2") (pinfunction "2_2") (pintype "passive"))
      (node (ref "R332") (pin "1") (pinfunction "1_1") (pintype "passive"))
    )
    (net (code "216") (name "Net-(R332-Pad2)") (class "Default")
      (node (ref "R332") (pin "2") (pinfunction "2_2") (pintype "passive"))
      (node (ref "R333") (pin "1") (pinfunction "1_1") (pintype "passive"))
    )
    (net (code "217") (name "Net-(R335-Pad2)") (class "Default")
      (node (ref "R335") (pin "2") (pinfunction "2_2") (pintype "passive"))
      (node (ref "R336") (pin "1") (pinfunction "1_1") (pintype "passive"))
    )
    (net (code "218") (name "Net-(R336-Pad2)") (class "Default")
      (node (ref "R336") (pin "2") (pinfunction "2_2") (pintype "passive"))
      (node (ref "R337") (pin "1") (pinfunction "1_1") (pintype "passive"))
    )
    (net (code "219") (name "Net-(R337-Pad2)") (class "Default")
      (node (ref "R337") (pin "2") (pinfunction "2_2") (pintype "passive"))
      (node (ref "R338") (pin "1") (pinfunction "1_1") (pintype "passive"))
    )
    (net (code "220") (name "Net-(R338-Pad2)") (class "Default")
      (node (ref "R338") (pin "2") (pinfunction "2_2") (pintype "passive"))
      (node (ref "R339") (pin "1") (pinfunction "1_1") (pintype "passive"))
    )
    (net (code "221") (name "Net-(R339-Pad2)") (class "Default")
      (node (ref "R339") (pin "2") (pinfunction "2_2") (pintype "passive"))
      (node (ref "R340") (pin "1") (pinfunction "1_1") (pintype "passive"))
    )
    (net (code "222") (name "Net-(R340-Pad2)") (class "Default")
      (node (ref "R340") (pin "2") (pinfunction "2_2") (pintype "passive"))
      (node (ref "R341") (pin "1") (pinfunction "1_1") (pintype "passive"))
    )
    (net (code "223") (name "Net-(R341-Pad2)") (class "Default")
      (node (ref "R341") (pin "2") (pinfunction "2_2") (pintype "passive"))
      (node (ref "R342") (pin "1") (pinfunction "1_1") (pintype "passive"))
    )
    (net (code "224") (name "Net-(R342-Pad2)") (class "Default")
      (node (ref "R342") (pin "2") (pinfunction "2_2") (pintype "passive"))
      (node (ref "R343") (pin "1") (pinfunction "1_1") (pintype "passive"))
    )
    (net (code "225") (name "Net-(R343-Pad2)") (class "Default")
      (node (ref "R343") (pin "2") (pinfunction "2_2") (pintype "passive"))
      (node (ref "R344") (pin "1") (pinfunction "1_1") (pintype "passive"))
    )
    (net (code "226") (name "Net-(R347-Pad2)") (class "Default")
      (node (ref "R347") (pin "2") (pinfunction "2_2") (pintype "passive"))
      (node (ref "R348") (pin "1") (pinfunction "1_1") (pintype "passive"))
    )
    (net (code "227") (name "Net-(R348-Pad2)") (class "Default")
      (node (ref "R348") (pin "2") (pinfunction "2_2") (pintype "passive"))
      (node (ref "R349") (pin "1") (pinfunction "1_1") (pintype "passive"))
    )
    (net (code "228") (name "Net-(R349-Pad2)") (class "Default")
      (node (ref "R349") (pin "2") (pinfunction "2_2") (pintype "passive"))
      (node (ref "R350") (pin "1") (pinfunction "1_1") (pintype "passive"))
    )
    (net (code "229") (name "Net-(R350-Pad2)") (class "Default")
      (node (ref "R350") (pin "2") (pinfunction "2_2") (pintype "passive"))
      (node (ref "R351") (pin "1") (pinfunction "1_1") (pintype "passive"))
    )
    (net (code "230") (name "Net-(R351-Pad2)") (class "Default")
      (node (ref "R351") (pin "2") (pinfunction "2_2") (pintype "passive"))
      (node (ref "R352") (pin "1") (pinfunction "1_1") (pintype "passive"))
    )
    (net (code "231") (name "Net-(R352-Pad2)") (class "Default")
      (node (ref "R352") (pin "2") (pinfunction "2_2") (pintype "passive"))
      (node (ref "R353") (pin "1") (pinfunction "1_1") (pintype "passive"))
    )
    (net (code "232") (name "Net-(R353-Pad2)") (class "Default")
      (node (ref "R353") (pin "2") (pinfunction "2_2") (pintype "passive"))
      (node (ref "R354") (pin "1") (pinfunction "1_1") (pintype "passive"))
    )
    (net (code "233") (name "Net-(R354-Pad2)") (class "Default")
      (node (ref "R354") (pin "2") (pinfunction "2_2") (pintype "passive"))
      (node (ref "R355") (pin "1") (pinfunction "1_1") (pintype "passive"))
    )
    (net (code "234") (name "Net-(R355-Pad2)") (class "Default")
      (node (ref "R355") (pin "2") (pinfunction "2_2") (pintype "passive"))
      (node (ref "R356") (pin "1") (pinfunction "1_1") (pintype "passive"))
    )
    (net (code "235") (name "Net-(R358-Pad2)") (class "Default")
      (node (ref "R358") (pin "2") (pinfunction "2_2") (pintype "passive"))
      (node (ref "R359") (pin "1") (pinfunction "1_1") (pintype "passive"))
    )
    (net (code "236") (name "Net-(R359-Pad2)") (class "Default")
      (node (ref "R359") (pin "2") (pinfunction "2_2") (pintype "passive"))
      (node (ref "R360") (pin "1") (pinfunction "1_1") (pintype "passive"))
    )
    (net (code "237") (name "Net-(R360-Pad2)") (class "Default")
      (node (ref "R360") (pin "2") (pinfunction "2_2") (pintype "passive"))
      (node (ref "R361") (pin "1") (pinfunction "1_1") (pintype "passive"))
    )
    (net (code "238") (name "Net-(R361-Pad2)") (class "Default")
      (node (ref "R361") (pin "2") (pinfunction "2_2") (pintype "passive"))
      (node (ref "R362") (pin "1") (pinfunction "1_1") (pintype "passive"))
    )
    (net (code "239") (name "Net-(R362-Pad2)") (class "Default")
      (node (ref "R362") (pin "2") (pinfunction "2_2") (pintype "passive"))
      (node (ref "R363") (pin "1") (pinfunction "1_1") (pintype "passive"))
    )
    (net (code "240") (name "Net-(R363-Pad2)") (class "Default")
      (node (ref "R363") (pin "2") (pinfunction "2_2") (pintype "passive"))
      (node (ref "R364") (pin "1") (pinfunction "1_1") (pintype "passive"))
    )
    (net (code "241") (name "Net-(R364-Pad2)") (class "Default")
      (node (ref "R364") (pin "2") (pinfunction "2_2") (pintype "passive"))
      (node (ref "R365") (pin "1") (pinfunction "1_1") (pintype "passive"))
    )
    (net (code "242") (name "Net-(R365-Pad2)") (class "Default")
      (node (ref "R365") (pin "2") (pinfunction "2_2") (pintype "passive"))
      (node (ref "R366") (pin "1") (pinfunction "1_1") (pintype "passive"))
    )
    (net (code "243") (name "Net-(R366-Pad2)") (class "Default")
      (node (ref "R366") (pin "2") (pinfunction "2_2") (pintype "passive"))
      (node (ref "R367") (pin "1") (pinfunction "1_1") (pintype "passive"))
    )
    (net (code "244") (name "unconnected-(X1A-KL-Pad1)") (class "Default")
      (node (ref "X1") (pin "1") (pinfunction "KL_1") (pintype "passive"))
    )
    (net (code "245") (name "unconnected-(X2B-KL-Pad2)") (class "Default")
      (node (ref "X2") (pin "2") (pinfunction "KL_2") (pintype "passive"))
    )
    (net (code "246") (name "unconnected-(X5A-KL-Pad1)") (class "Default")
      (node (ref "X5") (pin "1") (pinfunction "KL_1") (pintype "passive"))
    )
    (net (code "247") (name "unconnected-(X6B-KL-Pad2)") (class "Default")
      (node (ref "X6") (pin "2") (pinfunction "KL_2") (pintype "passive"))
    )
    (net (code "248") (name "unconnected-(X7A-KL-Pad1)") (class "Default")
      (node (ref "X7") (pin "1") (pinfunction "KL_1") (pintype "passive"))
    )
    (net (code "249") (name "unconnected-(X8B-KL-Pad2)") (class "Default")
      (node (ref "X8") (pin "2") (pinfunction "KL_2") (pintype "passive"))
    )
    (net (code "250") (name "unconnected-(X9A-KL-Pad1)") (class "Default")
      (node (ref "X9") (pin "1") (pinfunction "KL_1") (pintype "passive"))
    )
    (net (code "251") (name "unconnected-(X10B-KL-Pad2)") (class "Default")
      (node (ref "X10") (pin "2") (pinfunction "KL_2") (pintype "passive"))
    )
    (net (code "252") (name "unconnected-(X11A-KL-Pad1)") (class "Default")
      (node (ref "X11") (pin "1") (pinfunction "KL_1") (pintype "passive"))
    )
    (net (code "253") (name "unconnected-(X12B-KL-Pad2)") (class "Default")
      (node (ref "X12") (pin "2") (pinfunction "KL_2") (pintype "passive"))
    )
    (net (code "254") (name "unconnected-(X13A-KL-Pad1)") (class "Default")
      (node (ref "X13") (pin "1") (pinfunction "KL_1") (pintype "passive"))
    )
    (net (code "255") (name "unconnected-(X14B-KL-Pad2)") (class "Default")
      (node (ref "X14") (pin "2") (pinfunction "KL_2") (pintype "passive"))
    )
    (net (code "256") (name "unconnected-(X15A-KL-Pad1)") (class "Default")
      (node (ref "X15") (pin "1") (pinfunction "KL_1") (pintype "passive"))
    )
    (net (code "257") (name "unconnected-(X16B-KL-Pad2)") (class "Default")
      (node (ref "X16") (pin "2") (pinfunction "KL_2") (pintype "passive"))
    )
    (net (code "258") (name "unconnected-(X17A-KL-Pad1)") (class "Default")
      (node (ref "X17") (pin "1") (pinfunction "KL_1") (pintype "passive"))
    )
    (net (code "259") (name "unconnected-(X18B-KL-Pad2)") (class "Default")
      (node (ref "X18") (pin "2") (pinfunction "KL_2") (pintype "passive"))
    )
    (net (code "260") (name "unconnected-(X25A-KL-Pad1)") (class "Default")
      (node (ref "X25") (pin "1") (pinfunction "KL_1") (pintype "passive"))
    )
    (net (code "261") (name "unconnected-(X26B-KL-Pad2)") (class "Default")
      (node (ref "X26") (pin "2") (pinfunction "KL_2") (pintype "passive"))
    )
    (net (code "262") (name "unconnected-(X27A-KL-Pad1)") (class "Default")
      (node (ref "X27") (pin "1") (pinfunction "KL_1") (pintype "passive"))
    )
    (net (code "263") (name "unconnected-(X28B-KL-Pad2)") (class "Default")
      (node (ref "X28") (pin "2") (pinfunction "KL_2") (pintype "passive"))
    )
    (net (code "264") (name "unconnected-(X29A-KL-Pad1)") (class "Default")
      (node (ref "X29") (pin "1") (pinfunction "KL_1") (pintype "passive"))
    )
    (net (code "265") (name "unconnected-(X30B-KL-Pad2)") (class "Default")
      (node (ref "X30") (pin "2") (pinfunction "KL_2") (pintype "passive"))
    )
    (net (code "266") (name "unconnected-(X31A-KL-Pad1)") (class "Default")
      (node (ref "X31") (pin "1") (pinfunction "KL_1") (pintype "passive"))
    )
    (net (code "267") (name "unconnected-(X32B-KL-Pad2)") (class "Default")
      (node (ref "X32") (pin "2") (pinfunction "KL_2") (pintype "passive"))
    )
  )
)
